# EP4CE55F23C8N_A.net
KiCad netlist of a schematic drawn in Altium Designer
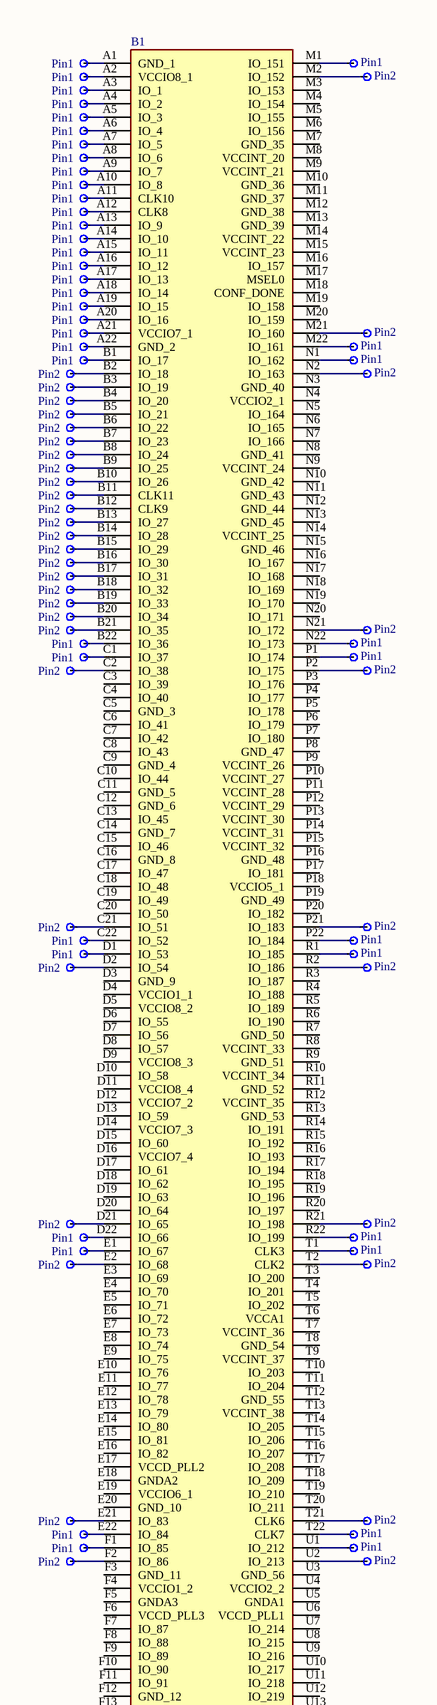
[diagram p0: EP4CE55F23C8N_A.SchDoc, top]
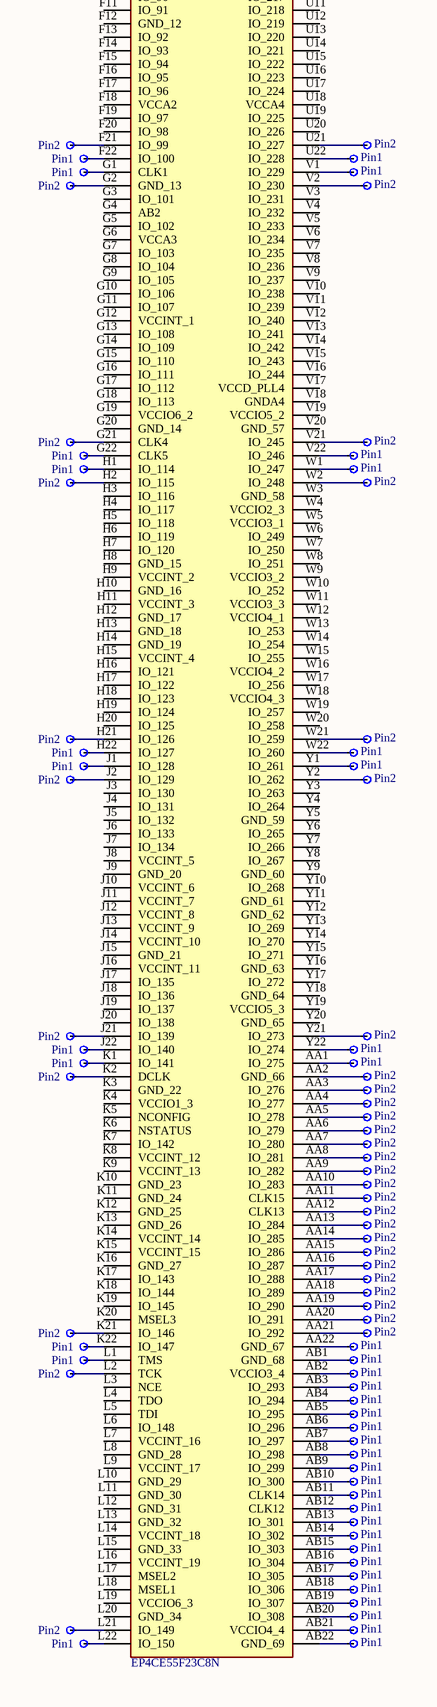
[diagram p1: EP4CE55F23C8N_A.SchDoc, bottom]

(export (version "E")
  (design (tool "Eeschema 10.0.6"))
  (components
    (comp (ref "B1")
      (value "EP4CE55F23C8N")
      (footprint "BGA484C100P22X22_2300X2300X240")
      (description "FPGA - Field Programmable Gate Array FPGA - Cyclone IV E 3491 LABs 324 IOs")
      (fields (field (name "MOUSER PART NUMBER") "989-EP4CE55F23C8N"))
      (libsource (lib "EP4CE55F23C8N") (part "EP4CE55F23C8N"))
    )
    (comp (ref "J1") (value "Pin1") (footprint "Pin1") (libsource (lib "Schlib1") (part "Pin1")))
    (comp (ref "J2") (value "Pin1") (footprint "Pin1") (libsource (lib "Schlib1") (part "Pin1")))
    (comp (ref "J3") (value "Pin1") (footprint "Pin1") (libsource (lib "Schlib1") (part "Pin1")))
    (comp (ref "J4") (value "Pin2") (footprint "Pin1") (libsource (lib "Schlib1") (part "Pin1")))
    (comp (ref "J5") (value "Pin1") (footprint "Pin1") (libsource (lib "Schlib1") (part "Pin1")))
    (comp (ref "J6") (value "Pin1") (footprint "Pin1") (libsource (lib "Schlib1") (part "Pin1")))
    (comp (ref "J7") (value "Pin1") (footprint "Pin1") (libsource (lib "Schlib1") (part "Pin1")))
    (comp (ref "J8") (value "Pin1") (footprint "Pin1") (libsource (lib "Schlib1") (part "Pin1")))
    (comp (ref "J9") (value "Pin1") (footprint "Pin1") (libsource (lib "Schlib1") (part "Pin1")))
    (comp (ref "J10") (value "Pin1") (footprint "Pin1") (libsource (lib "Schlib1") (part "Pin1")))
    (comp (ref "J11") (value "Pin1") (footprint "Pin1") (libsource (lib "Schlib1") (part "Pin1")))
    (comp (ref "J12") (value "Pin1") (footprint "Pin1") (libsource (lib "Schlib1") (part "Pin1")))
    (comp (ref "J13") (value "Pin1") (footprint "Pin1") (libsource (lib "Schlib1") (part "Pin1")))
    (comp (ref "J14") (value "Pin1") (footprint "Pin1") (libsource (lib "Schlib1") (part "Pin1")))
    (comp (ref "J15") (value "Pin1") (footprint "Pin1") (libsource (lib "Schlib1") (part "Pin1")))
    (comp (ref "J16") (value "Pin1") (footprint "Pin1") (libsource (lib "Schlib1") (part "Pin1")))
    (comp (ref "J17") (value "Pin1") (footprint "Pin1") (libsource (lib "Schlib1") (part "Pin1")))
    (comp (ref "J18") (value "Pin1") (footprint "Pin1") (libsource (lib "Schlib1") (part "Pin1")))
    (comp (ref "J19") (value "Pin1") (footprint "Pin1") (libsource (lib "Schlib1") (part "Pin1")))
    (comp (ref "J20") (value "Pin1") (footprint "Pin1") (libsource (lib "Schlib1") (part "Pin1")))
    (comp (ref "J21") (value "Pin1") (footprint "Pin1") (libsource (lib "Schlib1") (part "Pin1")))
    (comp (ref "J22") (value "Pin1") (footprint "Pin1") (libsource (lib "Schlib1") (part "Pin1")))
    (comp (ref "J23") (value "Pin1") (footprint "Pin1") (libsource (lib "Schlib1") (part "Pin1")))
    (comp (ref "J24") (value "Pin2") (footprint "Pin1") (libsource (lib "Schlib1") (part "Pin1")))
    (comp (ref "J25") (value "Pin1") (footprint "Pin1") (libsource (lib "Schlib1") (part "Pin1")))
    (comp (ref "J26") (value "Pin1") (footprint "Pin1") (libsource (lib "Schlib1") (part "Pin1")))
    (comp (ref "J27") (value "Pin1") (footprint "Pin1") (libsource (lib "Schlib1") (part "Pin1")))
    (comp (ref "J28") (value "Pin1") (footprint "Pin1") (libsource (lib "Schlib1") (part "Pin1")))
    (comp (ref "J29") (value "Pin2") (footprint "Pin1") (libsource (lib "Schlib1") (part "Pin1")))
    (comp (ref "J30") (value "Pin2") (footprint "Pin1") (libsource (lib "Schlib1") (part "Pin1")))
    (comp (ref "J31") (value "Pin2") (footprint "Pin1") (libsource (lib "Schlib1") (part "Pin1")))
    (comp (ref "J32") (value "Pin2") (footprint "Pin1") (libsource (lib "Schlib1") (part "Pin1")))
    (comp (ref "J33") (value "Pin2") (footprint "Pin1") (libsource (lib "Schlib1") (part "Pin1")))
    (comp (ref "J34") (value "Pin2") (footprint "Pin1") (libsource (lib "Schlib1") (part "Pin1")))
    (comp (ref "J35") (value "Pin2") (footprint "Pin1") (libsource (lib "Schlib1") (part "Pin1")))
    (comp (ref "J36") (value "Pin2") (footprint "Pin1") (libsource (lib "Schlib1") (part "Pin1")))
    (comp (ref "J37") (value "Pin2") (footprint "Pin1") (libsource (lib "Schlib1") (part "Pin1")))
    (comp (ref "J38") (value "Pin2") (footprint "Pin1") (libsource (lib "Schlib1") (part "Pin1")))
    (comp (ref "J39") (value "Pin2") (footprint "Pin1") (libsource (lib "Schlib1") (part "Pin1")))
    (comp (ref "J40") (value "Pin2") (footprint "Pin1") (libsource (lib "Schlib1") (part "Pin1")))
    (comp (ref "J41") (value "Pin2") (footprint "Pin1") (libsource (lib "Schlib1") (part "Pin1")))
    (comp (ref "J42") (value "Pin2") (footprint "Pin1") (libsource (lib "Schlib1") (part "Pin1")))
    (comp (ref "J43") (value "Pin2") (footprint "Pin1") (libsource (lib "Schlib1") (part "Pin1")))
    (comp (ref "J44") (value "Pin2") (footprint "Pin1") (libsource (lib "Schlib1") (part "Pin1")))
    (comp (ref "J45") (value "Pin2") (footprint "Pin1") (libsource (lib "Schlib1") (part "Pin1")))
    (comp (ref "J46") (value "Pin2") (footprint "Pin1") (libsource (lib "Schlib1") (part "Pin1")))
    (comp (ref "J47") (value "Pin2") (footprint "Pin1") (libsource (lib "Schlib1") (part "Pin1")))
    (comp (ref "J48") (value "Pin2") (footprint "Pin1") (libsource (lib "Schlib1") (part "Pin1")))
    (comp (ref "J49") (value "Pin2") (footprint "Pin1") (libsource (lib "Schlib1") (part "Pin1")))
    (comp (ref "J50") (value "Pin2") (footprint "Pin1") (libsource (lib "Schlib1") (part "Pin1")))
    (comp (ref "J51") (value "Pin1") (footprint "Pin1") (libsource (lib "Schlib1") (part "Pin1")))
    (comp (ref "J52") (value "Pin1") (footprint "Pin1") (libsource (lib "Schlib1") (part "Pin1")))
    (comp (ref "J53") (value "Pin1") (footprint "Pin1") (libsource (lib "Schlib1") (part "Pin1")))
    (comp (ref "J54") (value "Pin1") (footprint "Pin1") (libsource (lib "Schlib1") (part "Pin1")))
    (comp (ref "J55") (value "Pin2") (footprint "Pin1") (libsource (lib "Schlib1") (part "Pin1")))
    (comp (ref "J56") (value "Pin2") (footprint "Pin1") (libsource (lib "Schlib1") (part "Pin1")))
    (comp (ref "J57") (value "Pin2") (footprint "Pin1") (libsource (lib "Schlib1") (part "Pin1")))
    (comp (ref "J58") (value "Pin2") (footprint "Pin1") (libsource (lib "Schlib1") (part "Pin1")))
    (comp (ref "J59") (value "Pin1") (footprint "Pin1") (libsource (lib "Schlib1") (part "Pin1")))
    (comp (ref "J60") (value "Pin1") (footprint "Pin1") (libsource (lib "Schlib1") (part "Pin1")))
    (comp (ref "J61") (value "Pin1") (footprint "Pin1") (libsource (lib "Schlib1") (part "Pin1")))
    (comp (ref "J62") (value "Pin1") (footprint "Pin1") (libsource (lib "Schlib1") (part "Pin1")))
    (comp (ref "J63") (value "Pin2") (footprint "Pin1") (libsource (lib "Schlib1") (part "Pin1")))
    (comp (ref "J64") (value "Pin2") (footprint "Pin1") (libsource (lib "Schlib1") (part "Pin1")))
    (comp (ref "J65") (value "Pin2") (footprint "Pin1") (libsource (lib "Schlib1") (part "Pin1")))
    (comp (ref "J66") (value "Pin2") (footprint "Pin1") (libsource (lib "Schlib1") (part "Pin1")))
    (comp (ref "J67") (value "Pin1") (footprint "Pin1") (libsource (lib "Schlib1") (part "Pin1")))
    (comp (ref "J68") (value "Pin1") (footprint "Pin1") (libsource (lib "Schlib1") (part "Pin1")))
    (comp (ref "J69") (value "Pin1") (footprint "Pin1") (libsource (lib "Schlib1") (part "Pin1")))
    (comp (ref "J70") (value "Pin1") (footprint "Pin1") (libsource (lib "Schlib1") (part "Pin1")))
    (comp (ref "J71") (value "Pin2") (footprint "Pin1") (libsource (lib "Schlib1") (part "Pin1")))
    (comp (ref "J72") (value "Pin2") (footprint "Pin1") (libsource (lib "Schlib1") (part "Pin1")))
    (comp (ref "J73") (value "Pin2") (footprint "Pin1") (libsource (lib "Schlib1") (part "Pin1")))
    (comp (ref "J74") (value "Pin2") (footprint "Pin1") (libsource (lib "Schlib1") (part "Pin1")))
    (comp (ref "J75") (value "Pin1") (footprint "Pin1") (libsource (lib "Schlib1") (part "Pin1")))
    (comp (ref "J76") (value "Pin1") (footprint "Pin1") (libsource (lib "Schlib1") (part "Pin1")))
    (comp (ref "J77") (value "Pin1") (footprint "Pin1") (libsource (lib "Schlib1") (part "Pin1")))
    (comp (ref "J78") (value "Pin1") (footprint "Pin1") (libsource (lib "Schlib1") (part "Pin1")))
    (comp (ref "J79") (value "Pin2") (footprint "Pin1") (libsource (lib "Schlib1") (part "Pin1")))
    (comp (ref "J80") (value "Pin2") (footprint "Pin1") (libsource (lib "Schlib1") (part "Pin1")))
    (comp (ref "J81") (value "Pin2") (footprint "Pin1") (libsource (lib "Schlib1") (part "Pin1")))
    (comp (ref "J82") (value "Pin2") (footprint "Pin1") (libsource (lib "Schlib1") (part "Pin1")))
    (comp (ref "J83") (value "Pin1") (footprint "Pin1") (libsource (lib "Schlib1") (part "Pin1")))
    (comp (ref "J84") (value "Pin1") (footprint "Pin1") (libsource (lib "Schlib1") (part "Pin1")))
    (comp (ref "J85") (value "Pin1") (footprint "Pin1") (libsource (lib "Schlib1") (part "Pin1")))
    (comp (ref "J86") (value "Pin1") (footprint "Pin1") (libsource (lib "Schlib1") (part "Pin1")))
    (comp (ref "J87") (value "Pin2") (footprint "Pin1") (libsource (lib "Schlib1") (part "Pin1")))
    (comp (ref "J88") (value "Pin2") (footprint "Pin1") (libsource (lib "Schlib1") (part "Pin1")))
    (comp (ref "J89") (value "Pin2") (footprint "Pin1") (libsource (lib "Schlib1") (part "Pin1")))
    (comp (ref "J90") (value "Pin2") (footprint "Pin1") (libsource (lib "Schlib1") (part "Pin1")))
    (comp (ref "J91") (value "Pin1") (footprint "Pin1") (libsource (lib "Schlib1") (part "Pin1")))
    (comp (ref "J92") (value "Pin1") (footprint "Pin1") (libsource (lib "Schlib1") (part "Pin1")))
    (comp (ref "J93") (value "Pin1") (footprint "Pin1") (libsource (lib "Schlib1") (part "Pin1")))
    (comp (ref "J94") (value "Pin1") (footprint "Pin1") (libsource (lib "Schlib1") (part "Pin1")))
    (comp (ref "J95") (value "Pin2") (footprint "Pin1") (libsource (lib "Schlib1") (part "Pin1")))
    (comp (ref "J96") (value "Pin2") (footprint "Pin1") (libsource (lib "Schlib1") (part "Pin1")))
    (comp (ref "J97") (value "Pin2") (footprint "Pin1") (libsource (lib "Schlib1") (part "Pin1")))
    (comp (ref "J98") (value "Pin2") (footprint "Pin1") (libsource (lib "Schlib1") (part "Pin1")))
    (comp (ref "J99") (value "Pin1") (footprint "Pin1") (libsource (lib "Schlib1") (part "Pin1")))
    (comp (ref "J100") (value "Pin1") (footprint "Pin1") (libsource (lib "Schlib1") (part "Pin1")))
    (comp (ref "J101") (value "Pin1") (footprint "Pin1") (libsource (lib "Schlib1") (part "Pin1")))
    (comp (ref "J102") (value "Pin1") (footprint "Pin1") (libsource (lib "Schlib1") (part "Pin1")))
    (comp (ref "J103") (value "Pin2") (footprint "Pin1") (libsource (lib "Schlib1") (part "Pin1")))
    (comp (ref "J104") (value "Pin2") (footprint "Pin1") (libsource (lib "Schlib1") (part "Pin1")))
    (comp (ref "J105") (value "Pin2") (footprint "Pin1") (libsource (lib "Schlib1") (part "Pin1")))
    (comp (ref "J106") (value "Pin2") (footprint "Pin1") (libsource (lib "Schlib1") (part "Pin1")))
    (comp (ref "J107") (value "Pin1") (footprint "Pin1") (libsource (lib "Schlib1") (part "Pin1")))
    (comp (ref "J108") (value "Pin1") (footprint "Pin1") (libsource (lib "Schlib1") (part "Pin1")))
    (comp (ref "J109") (value "Pin1") (footprint "Pin1") (libsource (lib "Schlib1") (part "Pin1")))
    (comp (ref "J110") (value "Pin1") (footprint "Pin1") (libsource (lib "Schlib1") (part "Pin1")))
    (comp (ref "J111") (value "Pin2") (footprint "Pin1") (libsource (lib "Schlib1") (part "Pin1")))
    (comp (ref "J112") (value "Pin2") (footprint "Pin1") (libsource (lib "Schlib1") (part "Pin1")))
    (comp (ref "J113") (value "Pin2") (footprint "Pin1") (libsource (lib "Schlib1") (part "Pin1")))
    (comp (ref "J114") (value "Pin2") (footprint "Pin1") (libsource (lib "Schlib1") (part "Pin1")))
    (comp (ref "J115") (value "Pin2") (footprint "Pin1") (libsource (lib "Schlib1") (part "Pin1")))
    (comp (ref "J116") (value "Pin2") (footprint "Pin1") (libsource (lib "Schlib1") (part "Pin1")))
    (comp (ref "J117") (value "Pin2") (footprint "Pin1") (libsource (lib "Schlib1") (part "Pin1")))
    (comp (ref "J118") (value "Pin2") (footprint "Pin1") (libsource (lib "Schlib1") (part "Pin1")))
    (comp (ref "J119") (value "Pin2") (footprint "Pin1") (libsource (lib "Schlib1") (part "Pin1")))
    (comp (ref "J120") (value "Pin2") (footprint "Pin1") (libsource (lib "Schlib1") (part "Pin1")))
    (comp (ref "J121") (value "Pin2") (footprint "Pin1") (libsource (lib "Schlib1") (part "Pin1")))
    (comp (ref "J122") (value "Pin2") (footprint "Pin1") (libsource (lib "Schlib1") (part "Pin1")))
    (comp (ref "J123") (value "Pin2") (footprint "Pin1") (libsource (lib "Schlib1") (part "Pin1")))
    (comp (ref "J124") (value "Pin2") (footprint "Pin1") (libsource (lib "Schlib1") (part "Pin1")))
    (comp (ref "J125") (value "Pin2") (footprint "Pin1") (libsource (lib "Schlib1") (part "Pin1")))
    (comp (ref "J126") (value "Pin2") (footprint "Pin1") (libsource (lib "Schlib1") (part "Pin1")))
    (comp (ref "J127") (value "Pin2") (footprint "Pin1") (libsource (lib "Schlib1") (part "Pin1")))
    (comp (ref "J128") (value "Pin2") (footprint "Pin1") (libsource (lib "Schlib1") (part "Pin1")))
    (comp (ref "J129") (value "Pin2") (footprint "Pin1") (libsource (lib "Schlib1") (part "Pin1")))
    (comp (ref "J130") (value "Pin2") (footprint "Pin1") (libsource (lib "Schlib1") (part "Pin1")))
    (comp (ref "J131") (value "Pin2") (footprint "Pin1") (libsource (lib "Schlib1") (part "Pin1")))
    (comp (ref "J132") (value "Pin2") (footprint "Pin1") (libsource (lib "Schlib1") (part "Pin1")))
    (comp (ref "J133") (value "Pin1") (footprint "Pin1") (libsource (lib "Schlib1") (part "Pin1")))
    (comp (ref "J134") (value "Pin1") (footprint "Pin1") (libsource (lib "Schlib1") (part "Pin1")))
    (comp (ref "J135") (value "Pin1") (footprint "Pin1") (libsource (lib "Schlib1") (part "Pin1")))
    (comp (ref "J136") (value "Pin1") (footprint "Pin1") (libsource (lib "Schlib1") (part "Pin1")))
    (comp (ref "J137") (value "Pin2") (footprint "Pin1") (libsource (lib "Schlib1") (part "Pin1")))
    (comp (ref "J138") (value "Pin1") (footprint "Pin1") (libsource (lib "Schlib1") (part "Pin1")))
    (comp (ref "J139") (value "Pin1") (footprint "Pin1") (libsource (lib "Schlib1") (part "Pin1")))
    (comp (ref "J140") (value "Pin1") (footprint "Pin1") (libsource (lib "Schlib1") (part "Pin1")))
    (comp (ref "J141") (value "Pin1") (footprint "Pin1") (libsource (lib "Schlib1") (part "Pin1")))
    (comp (ref "J142") (value "Pin1") (footprint "Pin1") (libsource (lib "Schlib1") (part "Pin1")))
    (comp (ref "J143") (value "Pin1") (footprint "Pin1") (libsource (lib "Schlib1") (part "Pin1")))
    (comp (ref "J144") (value "Pin1") (footprint "Pin1") (libsource (lib "Schlib1") (part "Pin1")))
    (comp (ref "J145") (value "Pin1") (footprint "Pin1") (libsource (lib "Schlib1") (part "Pin1")))
    (comp (ref "J146") (value "Pin1") (footprint "Pin1") (libsource (lib "Schlib1") (part "Pin1")))
    (comp (ref "J147") (value "Pin1") (footprint "Pin1") (libsource (lib "Schlib1") (part "Pin1")))
    (comp (ref "J148") (value "Pin1") (footprint "Pin1") (libsource (lib "Schlib1") (part "Pin1")))
    (comp (ref "J149") (value "Pin1") (footprint "Pin1") (libsource (lib "Schlib1") (part "Pin1")))
    (comp (ref "J150") (value "Pin1") (footprint "Pin1") (libsource (lib "Schlib1") (part "Pin1")))
    (comp (ref "J151") (value "Pin1") (footprint "Pin1") (libsource (lib "Schlib1") (part "Pin1")))
    (comp (ref "J152") (value "Pin1") (footprint "Pin1") (libsource (lib "Schlib1") (part "Pin1")))
    (comp (ref "J153") (value "Pin1") (footprint "Pin1") (libsource (lib "Schlib1") (part "Pin1")))
    (comp (ref "J154") (value "Pin1") (footprint "Pin1") (libsource (lib "Schlib1") (part "Pin1")))
    (comp (ref "J155") (value "Pin1") (footprint "Pin1") (libsource (lib "Schlib1") (part "Pin1")))
    (comp (ref "J156") (value "Pin1") (footprint "Pin1") (libsource (lib "Schlib1") (part "Pin1")))
    (comp (ref "J157") (value "Pin2") (footprint "Pin1") (libsource (lib "Schlib1") (part "Pin1")))
    (comp (ref "J158") (value "Pin1") (footprint "Pin1") (libsource (lib "Schlib1") (part "Pin1")))
    (comp (ref "J159") (value "Pin1") (footprint "Pin1") (libsource (lib "Schlib1") (part "Pin1")))
    (comp (ref "J160") (value "Pin1") (footprint "Pin1") (libsource (lib "Schlib1") (part "Pin1")))
  )
  (nets
    (net (code "1") (name "Net-(B1-CLK1)") (class "Default")
      (node (ref "B1") (pin "G1") (pinfunction "CLK1_G1") (pintype "passive"))
      (node (ref "J85") (pin "1") (pinfunction "1_1") (pintype "passive"))
    )
    (net (code "2") (name "Net-(B1-CLK2)") (class "Default")
      (node (ref "B1") (pin "T2") (pinfunction "CLK2_T2") (pintype "passive"))
      (node (ref "J72") (pin "1") (pinfunction "1_1") (pintype "passive"))
    )
    (net (code "3") (name "Net-(B1-CLK3)") (class "Default")
      (node (ref "B1") (pin "T1") (pinfunction "CLK3_T1") (pintype "passive"))
      (node (ref "J70") (pin "1") (pinfunction "1_1") (pintype "passive"))
    )
    (net (code "4") (name "Net-(B1-CLK4)") (class "Default")
      (node (ref "B1") (pin "G21") (pinfunction "CLK4_G21") (pintype "passive"))
      (node (ref "J89") (pin "1") (pinfunction "1_1") (pintype "passive"))
    )
    (net (code "5") (name "Net-(B1-CLK5)") (class "Default")
      (node (ref "B1") (pin "G22") (pinfunction "CLK5_G22") (pintype "passive"))
      (node (ref "J91") (pin "1") (pinfunction "1_1") (pintype "passive"))
    )
    (net (code "6") (name "Net-(B1-CLK6)") (class "Default")
      (node (ref "B1") (pin "T21") (pinfunction "CLK6_T21") (pintype "passive"))
      (node (ref "J74") (pin "1") (pinfunction "1_1") (pintype "passive"))
    )
    (net (code "7") (name "Net-(B1-CLK7)") (class "Default")
      (node (ref "B1") (pin "T22") (pinfunction "CLK7_T22") (pintype "passive"))
      (node (ref "J76") (pin "1") (pinfunction "1_1") (pintype "passive"))
    )
    (net (code "8") (name "Net-(B1-CLK8)") (class "Default")
      (node (ref "B1") (pin "A12") (pinfunction "CLK8_A12") (pintype "passive"))
      (node (ref "J14") (pin "1") (pinfunction "1_1") (pintype "passive"))
    )
    (net (code "9") (name "Net-(B1-CLK9)") (class "Default")
      (node (ref "B1") (pin "B12") (pinfunction "CLK9_B12") (pintype "passive"))
      (node (ref "J40") (pin "1") (pinfunction "1_1") (pintype "passive"))
    )
    (net (code "10") (name "Net-(B1-CLK10)") (class "Default")
      (node (ref "B1") (pin "A11") (pinfunction "CLK10_A11") (pintype "passive"))
      (node (ref "J13") (pin "1") (pinfunction "1_1") (pintype "passive"))
    )
    (net (code "11") (name "Net-(B1-CLK11)") (class "Default")
      (node (ref "B1") (pin "B11") (pinfunction "CLK11_B11") (pintype "passive"))
      (node (ref "J39") (pin "1") (pinfunction "1_1") (pintype "passive"))
    )
    (net (code "12") (name "Net-(B1-CLK12)") (class "Default")
      (node (ref "B1") (pin "AB12") (pinfunction "CLK12_AB12") (pintype "passive"))
      (node (ref "J148") (pin "1") (pinfunction "1_1") (pintype "passive"))
    )
    (net (code "13") (name "Net-(B1-CLK13)") (class "Default")
      (node (ref "B1") (pin "AA12") (pinfunction "CLK13_AA12") (pintype "passive"))
      (node (ref "J122") (pin "1") (pinfunction "1_1") (pintype "passive"))
    )
    (net (code "14") (name "Net-(B1-CLK14)") (class "Default")
      (node (ref "B1") (pin "AB11") (pinfunction "CLK14_AB11") (pintype "passive"))
      (node (ref "J147") (pin "1") (pinfunction "1_1") (pintype "passive"))
    )
    (net (code "15") (name "Net-(B1-CLK15)") (class "Default")
      (node (ref "B1") (pin "AA11") (pinfunction "CLK15_AA11") (pintype "passive"))
      (node (ref "J121") (pin "1") (pinfunction "1_1") (pintype "passive"))
    )
    (net (code "16") (name "Net-(B1-DCLK)") (class "Default")
      (node (ref "B1") (pin "K2") (pinfunction "DCLK_K2") (pintype "passive"))
      (node (ref "J111") (pin "1") (pinfunction "1_1") (pintype "passive"))
    )
    (net (code "17") (name "Net-(B1-GND_1)") (class "Default")
      (node (ref "B1") (pin "A1") (pinfunction "GND_1_A1") (pintype "passive"))
      (node (ref "J1") (pin "1") (pinfunction "1_1") (pintype "passive"))
    )
    (net (code "18") (name "Net-(B1-GND_2)") (class "Default")
      (node (ref "B1") (pin "A22") (pinfunction "GND_2_A22") (pintype "passive"))
      (node (ref "J25") (pin "1") (pinfunction "1_1") (pintype "passive"))
    )
    (net (code "19") (name "Net-(B1-GND_13)") (class "Default")
      (node (ref "B1") (pin "G2") (pinfunction "GND_13_G2") (pintype "passive"))
      (node (ref "J87") (pin "1") (pinfunction "1_1") (pintype "passive"))
    )
    (net (code "20") (name "Net-(B1-GND_66)") (class "Default")
      (node (ref "B1") (pin "AA2") (pinfunction "GND_66_AA2") (pintype "passive"))
      (node (ref "J112") (pin "1") (pinfunction "1_1") (pintype "passive"))
    )
    (net (code "21") (name "Net-(B1-GND_67)") (class "Default")
      (node (ref "B1") (pin "AA22") (pinfunction "GND_67_AA22") (pintype "passive"))
      (node (ref "J134") (pin "1") (pinfunction "1_1") (pintype "passive"))
    )
    (net (code "22") (name "Net-(B1-GND_68)") (class "Default")
      (node (ref "B1") (pin "AB1") (pinfunction "GND_68_AB1") (pintype "passive"))
      (node (ref "J136") (pin "1") (pinfunction "1_1") (pintype "passive"))
    )
    (net (code "23") (name "Net-(B1-GND_69)") (class "Default")
      (node (ref "B1") (pin "AB22") (pinfunction "GND_69_AB22") (pintype "passive"))
      (node (ref "J160") (pin "1") (pinfunction "1_1") (pintype "passive"))
    )
    (net (code "24") (name "Net-(B1-IO_1)") (class "Default")
      (node (ref "B1") (pin "A3") (pinfunction "IO_1_A3") (pintype "passive"))
      (node (ref "J5") (pin "1") (pinfunction "1_1") (pintype "passive"))
    )
    (net (code "25") (name "Net-(B1-IO_2)") (class "Default")
      (node (ref "B1") (pin "A4") (pinfunction "IO_2_A4") (pintype "passive"))
      (node (ref "J6") (pin "1") (pinfunction "1_1") (pintype "passive"))
    )
    (net (code "26") (name "Net-(B1-IO_3)") (class "Default")
      (node (ref "B1") (pin "A5") (pinfunction "IO_3_A5") (pintype "passive"))
      (node (ref "J7") (pin "1") (pinfunction "1_1") (pintype "passive"))
    )
    (net (code "27") (name "Net-(B1-IO_4)") (class "Default")
      (node (ref "B1") (pin "A6") (pinfunction "IO_4_A6") (pintype "passive"))
      (node (ref "J8") (pin "1") (pinfunction "1_1") (pintype "passive"))
    )
    (net (code "28") (name "Net-(B1-IO_5)") (class "Default")
      (node (ref "B1") (pin "A7") (pinfunction "IO_5_A7") (pintype "passive"))
      (node (ref "J9") (pin "1") (pinfunction "1_1") (pintype "passive"))
    )
    (net (code "29") (name "Net-(B1-IO_6)") (class "Default")
      (node (ref "B1") (pin "A8") (pinfunction "IO_6_A8") (pintype "passive"))
      (node (ref "J10") (pin "1") (pinfunction "1_1") (pintype "passive"))
    )
    (net (code "30") (name "Net-(B1-IO_7)") (class "Default")
      (node (ref "B1") (pin "A9") (pinfunction "IO_7_A9") (pintype "passive"))
      (node (ref "J11") (pin "1") (pinfunction "1_1") (pintype "passive"))
    )
    (net (code "31") (name "Net-(B1-IO_8)") (class "Default")
      (node (ref "B1") (pin "A10") (pinfunction "IO_8_A10") (pintype "passive"))
      (node (ref "J12") (pin "1") (pinfunction "1_1") (pintype "passive"))
    )
    (net (code "32") (name "Net-(B1-IO_9)") (class "Default")
      (node (ref "B1") (pin "A13") (pinfunction "IO_9_A13") (pintype "passive"))
      (node (ref "J15") (pin "1") (pinfunction "1_1") (pintype "passive"))
    )
    (net (code "33") (name "Net-(B1-IO_10)") (class "Default")
      (node (ref "B1") (pin "A14") (pinfunction "IO_10_A14") (pintype "passive"))
      (node (ref "J16") (pin "1") (pinfunction "1_1") (pintype "passive"))
    )
    (net (code "34") (name "Net-(B1-IO_11)") (class "Default")
      (node (ref "B1") (pin "A15") (pinfunction "IO_11_A15") (pintype "passive"))
      (node (ref "J17") (pin "1") (pinfunction "1_1") (pintype "passive"))
    )
    (net (code "35") (name "Net-(B1-IO_12)") (class "Default")
      (node (ref "B1") (pin "A16") (pinfunction "IO_12_A16") (pintype "passive"))
      (node (ref "J18") (pin "1") (pinfunction "1_1") (pintype "passive"))
    )
    (net (code "36") (name "Net-(B1-IO_13)") (class "Default")
      (node (ref "B1") (pin "A17") (pinfunction "IO_13_A17") (pintype "passive"))
      (node (ref "J19") (pin "1") (pinfunction "1_1") (pintype "passive"))
    )
    (net (code "37") (name "Net-(B1-IO_14)") (class "Default")
      (node (ref "B1") (pin "A18") (pinfunction "IO_14_A18") (pintype "passive"))
      (node (ref "J20") (pin "1") (pinfunction "1_1") (pintype "passive"))
    )
    (net (code "38") (name "Net-(B1-IO_15)") (class "Default")
      (node (ref "B1") (pin "A19") (pinfunction "IO_15_A19") (pintype "passive"))
      (node (ref "J21") (pin "1") (pinfunction "1_1") (pintype "passive"))
    )
    (net (code "39") (name "Net-(B1-IO_16)") (class "Default")
      (node (ref "B1") (pin "A20") (pinfunction "IO_16_A20") (pintype "passive"))
      (node (ref "J22") (pin "1") (pinfunction "1_1") (pintype "passive"))
    )
    (net (code "40") (name "Net-(B1-IO_17)") (class "Default")
      (node (ref "B1") (pin "B1") (pinfunction "IO_17_B1") (pintype "passive"))
      (node (ref "J27") (pin "1") (pinfunction "1_1") (pintype "passive"))
    )
    (net (code "41") (name "Net-(B1-IO_18)") (class "Default")
      (node (ref "B1") (pin "B2") (pinfunction "IO_18_B2") (pintype "passive"))
      (node (ref "J29") (pin "1") (pinfunction "1_1") (pintype "passive"))
    )
    (net (code "42") (name "Net-(B1-IO_19)") (class "Default")
      (node (ref "B1") (pin "B3") (pinfunction "IO_19_B3") (pintype "passive"))
      (node (ref "J31") (pin "1") (pinfunction "1_1") (pintype "passive"))
    )
    (net (code "43") (name "Net-(B1-IO_20)") (class "Default")
      (node (ref "B1") (pin "B4") (pinfunction "IO_20_B4") (pintype "passive"))
      (node (ref "J32") (pin "1") (pinfunction "1_1") (pintype "passive"))
    )
    (net (code "44") (name "Net-(B1-IO_21)") (class "Default")
      (node (ref "B1") (pin "B5") (pinfunction "IO_21_B5") (pintype "passive"))
      (node (ref "J33") (pin "1") (pinfunction "1_1") (pintype "passive"))
    )
    (net (code "45") (name "Net-(B1-IO_22)") (class "Default")
      (node (ref "B1") (pin "B6") (pinfunction "IO_22_B6") (pintype "passive"))
      (node (ref "J34") (pin "1") (pinfunction "1_1") (pintype "passive"))
    )
    (net (code "46") (name "Net-(B1-IO_23)") (class "Default")
      (node (ref "B1") (pin "B7") (pinfunction "IO_23_B7") (pintype "passive"))
      (node (ref "J35") (pin "1") (pinfunction "1_1") (pintype "passive"))
    )
    (net (code "47") (name "Net-(B1-IO_24)") (class "Default")
      (node (ref "B1") (pin "B8") (pinfunction "IO_24_B8") (pintype "passive"))
      (node (ref "J36") (pin "1") (pinfunction "1_1") (pintype "passive"))
    )
    (net (code "48") (name "Net-(B1-IO_25)") (class "Default")
      (node (ref "B1") (pin "B9") (pinfunction "IO_25_B9") (pintype "passive"))
      (node (ref "J37") (pin "1") (pinfunction "1_1") (pintype "passive"))
    )
    (net (code "49") (name "Net-(B1-IO_26)") (class "Default")
      (node (ref "B1") (pin "B10") (pinfunction "IO_26_B10") (pintype "passive"))
      (node (ref "J38") (pin "1") (pinfunction "1_1") (pintype "passive"))
    )
    (net (code "50") (name "Net-(B1-IO_27)") (class "Default")
      (node (ref "B1") (pin "B13") (pinfunction "IO_27_B13") (pintype "passive"))
      (node (ref "J41") (pin "1") (pinfunction "1_1") (pintype "passive"))
    )
    (net (code "51") (name "Net-(B1-IO_28)") (class "Default")
      (node (ref "B1") (pin "B14") (pinfunction "IO_28_B14") (pintype "passive"))
      (node (ref "J42") (pin "1") (pinfunction "1_1") (pintype "passive"))
    )
    (net (code "52") (name "Net-(B1-IO_29)") (class "Default")
      (node (ref "B1") (pin "B15") (pinfunction "IO_29_B15") (pintype "passive"))
      (node (ref "J43") (pin "1") (pinfunction "1_1") (pintype "passive"))
    )
    (net (code "53") (name "Net-(B1-IO_30)") (class "Default")
      (node (ref "B1") (pin "B16") (pinfunction "IO_30_B16") (pintype "passive"))
      (node (ref "J44") (pin "1") (pinfunction "1_1") (pintype "passive"))
    )
    (net (code "54") (name "Net-(B1-IO_31)") (class "Default")
      (node (ref "B1") (pin "B17") (pinfunction "IO_31_B17") (pintype "passive"))
      (node (ref "J45") (pin "1") (pinfunction "1_1") (pintype "passive"))
    )
    (net (code "55") (name "Net-(B1-IO_32)") (class "Default")
      (node (ref "B1") (pin "B18") (pinfunction "IO_32_B18") (pintype "passive"))
      (node (ref "J46") (pin "1") (pinfunction "1_1") (pintype "passive"))
    )
    (net (code "56") (name "Net-(B1-IO_33)") (class "Default")
      (node (ref "B1") (pin "B19") (pinfunction "IO_33_B19") (pintype "passive"))
      (node (ref "J47") (pin "1") (pinfunction "1_1") (pintype "passive"))
    )
    (net (code "57") (name "Net-(B1-IO_34)") (class "Default")
      (node (ref "B1") (pin "B20") (pinfunction "IO_34_B20") (pintype "passive"))
      (node (ref "J48") (pin "1") (pinfunction "1_1") (pintype "passive"))
    )
    (net (code "58") (name "Net-(B1-IO_35)") (class "Default")
      (node (ref "B1") (pin "B21") (pinfunction "IO_35_B21") (pintype "passive"))
      (node (ref "J49") (pin "1") (pinfunction "1_1") (pintype "passive"))
    )
    (net (code "59") (name "Net-(B1-IO_36)") (class "Default")
      (node (ref "B1") (pin "B22") (pinfunction "IO_36_B22") (pintype "passive"))
      (node (ref "J51") (pin "1") (pinfunction "1_1") (pintype "passive"))
    )
    (net (code "60") (name "Net-(B1-IO_37)") (class "Default")
      (node (ref "B1") (pin "C1") (pinfunction "IO_37_C1") (pintype "passive"))
      (node (ref "J53") (pin "1") (pinfunction "1_1") (pintype "passive"))
    )
    (net (code "61") (name "Net-(B1-IO_38)") (class "Default")
      (node (ref "B1") (pin "C2") (pinfunction "IO_38_C2") (pintype "passive"))
      (node (ref "J55") (pin "1") (pinfunction "1_1") (pintype "passive"))
    )
    (net (code "62") (name "Net-(B1-IO_51)") (class "Default")
      (node (ref "B1") (pin "C21") (pinfunction "IO_51_C21") (pintype "passive"))
      (node (ref "J57") (pin "1") (pinfunction "1_1") (pintype "passive"))
    )
    (net (code "63") (name "Net-(B1-IO_52)") (class "Default")
      (node (ref "B1") (pin "C22") (pinfunction "IO_52_C22") (pintype "passive"))
      (node (ref "J59") (pin "1") (pinfunction "1_1") (pintype "passive"))
    )
    (net (code "64") (name "Net-(B1-IO_53)") (class "Default")
      (node (ref "B1") (pin "D1") (pinfunction "IO_53_D1") (pintype "passive"))
      (node (ref "J61") (pin "1") (pinfunction "1_1") (pintype "passive"))
    )
    (net (code "65") (name "Net-(B1-IO_54)") (class "Default")
      (node (ref "B1") (pin "D2") (pinfunction "IO_54_D2") (pintype "passive"))
      (node (ref "J63") (pin "1") (pinfunction "1_1") (pintype "passive"))
    )
    (net (code "66") (name "Net-(B1-IO_65)") (class "Default")
      (node (ref "B1") (pin "D21") (pinfunction "IO_65_D21") (pintype "passive"))
      (node (ref "J65") (pin "1") (pinfunction "1_1") (pintype "passive"))
    )
    (net (code "67") (name "Net-(B1-IO_66)") (class "Default")
      (node (ref "B1") (pin "D22") (pinfunction "IO_66_D22") (pintype "passive"))
      (node (ref "J67") (pin "1") (pinfunction "1_1") (pintype "passive"))
    )
    (net (code "68") (name "Net-(B1-IO_67)") (class "Default")
      (node (ref "B1") (pin "E1") (pinfunction "IO_67_E1") (pintype "passive"))
      (node (ref "J69") (pin "1") (pinfunction "1_1") (pintype "passive"))
    )
    (net (code "69") (name "Net-(B1-IO_68)") (class "Default")
      (node (ref "B1") (pin "E2") (pinfunction "IO_68_E2") (pintype "passive"))
      (node (ref "J71") (pin "1") (pinfunction "1_1") (pintype "passive"))
    )
    (net (code "70") (name "Net-(B1-IO_83)") (class "Default")
      (node (ref "B1") (pin "E21") (pinfunction "IO_83_E21") (pintype "passive"))
      (node (ref "J73") (pin "1") (pinfunction "1_1") (pintype "passive"))
    )
    (net (code "71") (name "Net-(B1-IO_84)") (class "Default")
      (node (ref "B1") (pin "E22") (pinfunction "IO_84_E22") (pintype "passive"))
      (node (ref "J75") (pin "1") (pinfunction "1_1") (pintype "passive"))
    )
    (net (code "72") (name "Net-(B1-IO_85)") (class "Default")
      (node (ref "B1") (pin "F1") (pinfunction "IO_85_F1") (pintype "passive"))
      (node (ref "J77") (pin "1") (pinfunction "1_1") (pintype "passive"))
    )
    (net (code "73") (name "Net-(B1-IO_86)") (class "Default")
      (node (ref "B1") (pin "F2") (pinfunction "IO_86_F2") (pintype "passive"))
      (node (ref "J79") (pin "1") (pinfunction "1_1") (pintype "passive"))
    )
    (net (code "74") (name "Net-(B1-IO_99)") (class "Default")
      (node (ref "B1") (pin "F21") (pinfunction "IO_99_F21") (pintype "passive"))
      (node (ref "J81") (pin "1") (pinfunction "1_1") (pintype "passive"))
    )
    (net (code "75") (name "Net-(B1-IO_100)") (class "Default")
      (node (ref "B1") (pin "F22") (pinfunction "IO_100_F22") (pintype "passive"))
      (node (ref "J83") (pin "1") (pinfunction "1_1") (pintype "passive"))
    )
    (net (code "76") (name "Net-(B1-IO_114)") (class "Default")
      (node (ref "B1") (pin "H1") (pinfunction "IO_114_H1") (pintype "passive"))
      (node (ref "J93") (pin "1") (pinfunction "1_1") (pintype "passive"))
    )
    (net (code "77") (name "Net-(B1-IO_115)") (class "Default")
      (node (ref "B1") (pin "H2") (pinfunction "IO_115_H2") (pintype "passive"))
      (node (ref "J95") (pin "1") (pinfunction "1_1") (pintype "passive"))
    )
    (net (code "78") (name "Net-(B1-IO_126)") (class "Default")
      (node (ref "B1") (pin "H21") (pinfunction "IO_126_H21") (pintype "passive"))
      (node (ref "J97") (pin "1") (pinfunction "1_1") (pintype "passive"))
    )
    (net (code "79") (name "Net-(B1-IO_127)") (class "Default")
      (node (ref "B1") (pin "H22") (pinfunction "IO_127_H22") (pintype "passive"))
      (node (ref "J99") (pin "1") (pinfunction "1_1") (pintype "passive"))
    )
    (net (code "80") (name "Net-(B1-IO_128)") (class "Default")
      (node (ref "B1") (pin "J1") (pinfunction "IO_128_J1") (pintype "passive"))
      (node (ref "J101") (pin "1") (pinfunction "1_1") (pintype "passive"))
    )
    (net (code "81") (name "Net-(B1-IO_129)") (class "Default")
      (node (ref "B1") (pin "J2") (pinfunction "IO_129_J2") (pintype "passive"))
      (node (ref "J103") (pin "1") (pinfunction "1_1") (pintype "passive"))
    )
    (net (code "82") (name "Net-(B1-IO_139)") (class "Default")
      (node (ref "B1") (pin "J21") (pinfunction "IO_139_J21") (pintype "passive"))
      (node (ref "J105") (pin "1") (pinfunction "1_1") (pintype "passive"))
    )
    (net (code "83") (name "Net-(B1-IO_140)") (class "Default")
      (node (ref "B1") (pin "J22") (pinfunction "IO_140_J22") (pintype "passive"))
      (node (ref "J107") (pin "1") (pinfunction "1_1") (pintype "passive"))
    )
    (net (code "84") (name "Net-(B1-IO_141)") (class "Default")
      (node (ref "B1") (pin "K1") (pinfunction "IO_141_K1") (pintype "passive"))
      (node (ref "J109") (pin "1") (pinfunction "1_1") (pintype "passive"))
    )
    (net (code "85") (name "Net-(B1-IO_146)") (class "Default")
      (node (ref "B1") (pin "K21") (pinfunction "IO_146_K21") (pintype "passive"))
      (node (ref "J131") (pin "1") (pinfunction "1_1") (pintype "passive"))
    )
    (net (code "86") (name "Net-(B1-IO_147)") (class "Default")
      (node (ref "B1") (pin "K22") (pinfunction "IO_147_K22") (pintype "passive"))
      (node (ref "J133") (pin "1") (pinfunction "1_1") (pintype "passive"))
    )
    (net (code "87") (name "Net-(B1-IO_149)") (class "Default")
      (node (ref "B1") (pin "L21") (pinfunction "IO_149_L21") (pintype "passive"))
      (node (ref "J157") (pin "1") (pinfunction "1_1") (pintype "passive"))
    )
    (net (code "88") (name "Net-(B1-IO_150)") (class "Default")
      (node (ref "B1") (pin "L22") (pinfunction "IO_150_L22") (pintype "passive"))
      (node (ref "J159") (pin "1") (pinfunction "1_1") (pintype "passive"))
    )
    (net (code "89") (name "Net-(B1-IO_151)") (class "Default")
      (node (ref "B1") (pin "M1") (pinfunction "IO_151_M1") (pintype "passive"))
      (node (ref "J2") (pin "1") (pinfunction "1_1") (pintype "passive"))
    )
    (net (code "90") (name "Net-(B1-IO_152)") (class "Default")
      (node (ref "B1") (pin "M2") (pinfunction "IO_152_M2") (pintype "passive"))
      (node (ref "J4") (pin "1") (pinfunction "1_1") (pintype "passive"))
    )
    (net (code "91") (name "Net-(B1-IO_160)") (class "Default")
      (node (ref "B1") (pin "M21") (pinfunction "IO_160_M21") (pintype "passive"))
      (node (ref "J24") (pin "1") (pinfunction "1_1") (pintype "passive"))
    )
    (net (code "92") (name "Net-(B1-IO_161)") (class "Default")
      (node (ref "B1") (pin "M22") (pinfunction "IO_161_M22") (pintype "passive"))
      (node (ref "J26") (pin "1") (pinfunction "1_1") (pintype "passive"))
    )
    (net (code "93") (name "Net-(B1-IO_162)") (class "Default")
      (node (ref "B1") (pin "N1") (pinfunction "IO_162_N1") (pintype "passive"))
      (node (ref "J28") (pin "1") (pinfunction "1_1") (pintype "passive"))
    )
    (net (code "94") (name "Net-(B1-IO_163)") (class "Default")
      (node (ref "B1") (pin "N2") (pinfunction "IO_163_N2") (pintype "passive"))
      (node (ref "J30") (pin "1") (pinfunction "1_1") (pintype "passive"))
    )
    (net (code "95") (name "Net-(B1-IO_172)") (class "Default")
      (node (ref "B1") (pin "N21") (pinfunction "IO_172_N21") (pintype "passive"))
      (node (ref "J50") (pin "1") (pinfunction "1_1") (pintype "passive"))
    )
    (net (code "96") (name "Net-(B1-IO_173)") (class "Default")
      (node (ref "B1") (pin "N22") (pinfunction "IO_173_N22") (pintype "passive"))
      (node (ref "J52") (pin "1") (pinfunction "1_1") (pintype "passive"))
    )
    (net (code "97") (name "Net-(B1-IO_174)") (class "Default")
      (node (ref "B1") (pin "P1") (pinfunction "IO_174_P1") (pintype "passive"))
      (node (ref "J54") (pin "1") (pinfunction "1_1") (pintype "passive"))
    )
    (net (code "98") (name "Net-(B1-IO_175)") (class "Default")
      (node (ref "B1") (pin "P2") (pinfunction "IO_175_P2") (pintype "passive"))
      (node (ref "J56") (pin "1") (pinfunction "1_1") (pintype "passive"))
    )
    (net (code "99") (name "Net-(B1-IO_183)") (class "Default")
      (node (ref "B1") (pin "P21") (pinfunction "IO_183_P21") (pintype "passive"))
      (node (ref "J58") (pin "1") (pinfunction "1_1") (pintype "passive"))
    )
    (net (code "100") (name "Net-(B1-IO_184)") (class "Default")
      (node (ref "B1") (pin "P22") (pinfunction "IO_184_P22") (pintype "passive"))
      (node (ref "J60") (pin "1") (pinfunction "1_1") (pintype "passive"))
    )
    (net (code "101") (name "Net-(B1-IO_185)") (class "Default")
      (node (ref "B1") (pin "R1") (pinfunction "IO_185_R1") (pintype "passive"))
      (node (ref "J62") (pin "1") (pinfunction "1_1") (pintype "passive"))
    )
    (net (code "102") (name "Net-(B1-IO_186)") (class "Default")
      (node (ref "B1") (pin "R2") (pinfunction "IO_186_R2") (pintype "passive"))
      (node (ref "J64") (pin "1") (pinfunction "1_1") (pintype "passive"))
    )
    (net (code "103") (name "Net-(B1-IO_198)") (class "Default")
      (node (ref "B1") (pin "R21") (pinfunction "IO_198_R21") (pintype "passive"))
      (node (ref "J66") (pin "1") (pinfunction "1_1") (pintype "passive"))
    )
    (net (code "104") (name "Net-(B1-IO_199)") (class "Default")
      (node (ref "B1") (pin "R22") (pinfunction "IO_199_R22") (pintype "passive"))
      (node (ref "J68") (pin "1") (pinfunction "1_1") (pintype "passive"))
    )
    (net (code "105") (name "Net-(B1-IO_212)") (class "Default")
      (node (ref "B1") (pin "U1") (pinfunction "IO_212_U1") (pintype "passive"))
      (node (ref "J78") (pin "1") (pinfunction "1_1") (pintype "passive"))
    )
    (net (code "106") (name "Net-(B1-IO_213)") (class "Default")
      (node (ref "B1") (pin "U2") (pinfunction "IO_213_U2") (pintype "passive"))
      (node (ref "J80") (pin "1") (pinfunction "1_1") (pintype "passive"))
    )
    (net (code "107") (name "Net-(B1-IO_227)") (class "Default")
      (node (ref "B1") (pin "U21") (pinfunction "IO_227_U21") (pintype "passive"))
      (node (ref "J82") (pin "1") (pinfunction "1_1") (pintype "passive"))
    )
    (net (code "108") (name "Net-(B1-IO_228)") (class "Default")
      (node (ref "B1") (pin "U22") (pinfunction "IO_228_U22") (pintype "passive"))
      (node (ref "J84") (pin "1") (pinfunction "1_1") (pintype "passive"))
    )
    (net (code "109") (name "Net-(B1-IO_229)") (class "Default")
      (node (ref "B1") (pin "V1") (pinfunction "IO_229_V1") (pintype "passive"))
      (node (ref "J86") (pin "1") (pinfunction "1_1") (pintype "passive"))
    )
    (net (code "110") (name "Net-(B1-IO_230)") (class "Default")
      (node (ref "B1") (pin "V2") (pinfunction "IO_230_V2") (pintype "passive"))
      (node (ref "J88") (pin "1") (pinfunction "1_1") (pintype "passive"))
    )
    (net (code "111") (name "Net-(B1-IO_245)") (class "Default")
      (node (ref "B1") (pin "V21") (pinfunction "IO_245_V21") (pintype "passive"))
      (node (ref "J90") (pin "1") (pinfunction "1_1") (pintype "passive"))
    )
    (net (code "112") (name "Net-(B1-IO_246)") (class "Default")
      (node (ref "B1") (pin "V22") (pinfunction "IO_246_V22") (pintype "passive"))
      (node (ref "J92") (pin "1") (pinfunction "1_1") (pintype "passive"))
    )
    (net (code "113") (name "Net-(B1-IO_247)") (class "Default")
      (node (ref "B1") (pin "W1") (pinfunction "IO_247_W1") (pintype "passive"))
      (node (ref "J94") (pin "1") (pinfunction "1_1") (pintype "passive"))
    )
    (net (code "114") (name "Net-(B1-IO_248)") (class "Default")
      (node (ref "B1") (pin "W2") (pinfunction "IO_248_W2") (pintype "passive"))
      (node (ref "J96") (pin "1") (pinfunction "1_1") (pintype "passive"))
    )
    (net (code "115") (name "Net-(B1-IO_259)") (class "Default")
      (node (ref "B1") (pin "W21") (pinfunction "IO_259_W21") (pintype "passive"))
      (node (ref "J98") (pin "1") (pinfunction "1_1") (pintype "passive"))
    )
    (net (code "116") (name "Net-(B1-IO_260)") (class "Default")
      (node (ref "B1") (pin "W22") (pinfunction "IO_260_W22") (pintype "passive"))
      (node (ref "J100") (pin "1") (pinfunction "1_1") (pintype "passive"))
    )
    (net (code "117") (name "Net-(B1-IO_261)") (class "Default")
      (node (ref "B1") (pin "Y1") (pinfunction "IO_261_Y1") (pintype "passive"))
      (node (ref "J102") (pin "1") (pinfunction "1_1") (pintype "passive"))
    )
    (net (code "118") (name "Net-(B1-IO_262)") (class "Default")
      (node (ref "B1") (pin "Y2") (pinfunction "IO_262_Y2") (pintype "passive"))
      (node (ref "J104") (pin "1") (pinfunction "1_1") (pintype "passive"))
    )
    (net (code "119") (name "Net-(B1-IO_273)") (class "Default")
      (node (ref "B1") (pin "Y21") (pinfunction "IO_273_Y21") (pintype "passive"))
      (node (ref "J106") (pin "1") (pinfunction "1_1") (pintype "passive"))
    )
    (net (code "120") (name "Net-(B1-IO_274)") (class "Default")
      (node (ref "B1") (pin "Y22") (pinfunction "IO_274_Y22") (pintype "passive"))
      (node (ref "J108") (pin "1") (pinfunction "1_1") (pintype "passive"))
    )
    (net (code "121") (name "Net-(B1-IO_275)") (class "Default")
      (node (ref "B1") (pin "AA1") (pinfunction "IO_275_AA1") (pintype "passive"))
      (node (ref "J110") (pin "1") (pinfunction "1_1") (pintype "passive"))
    )
    (net (code "122") (name "Net-(B1-IO_276)") (class "Default")
      (node (ref "B1") (pin "AA3") (pinfunction "IO_276_AA3") (pintype "passive"))
      (node (ref "J113") (pin "1") (pinfunction "1_1") (pintype "passive"))
    )
    (net (code "123") (name "Net-(B1-IO_277)") (class "Default")
      (node (ref "B1") (pin "AA4") (pinfunction "IO_277_AA4") (pintype "passive"))
      (node (ref "J114") (pin "1") (pinfunction "1_1") (pintype "passive"))
    )
    (net (code "124") (name "Net-(B1-IO_278)") (class "Default")
      (node (ref "B1") (pin "AA5") (pinfunction "IO_278_AA5") (pintype "passive"))
      (node (ref "J115") (pin "1") (pinfunction "1_1") (pintype "passive"))
    )
    (net (code "125") (name "Net-(B1-IO_279)") (class "Default")
      (node (ref "B1") (pin "AA6") (pinfunction "IO_279_AA6") (pintype "passive"))
      (node (ref "J116") (pin "1") (pinfunction "1_1") (pintype "passive"))
    )
    (net (code "126") (name "Net-(B1-IO_280)") (class "Default")
      (node (ref "B1") (pin "AA7") (pinfunction "IO_280_AA7") (pintype "passive"))
      (node (ref "J117") (pin "1") (pinfunction "1_1") (pintype "passive"))
    )
    (net (code "127") (name "Net-(B1-IO_281)") (class "Default")
      (node (ref "B1") (pin "AA8") (pinfunction "IO_281_AA8") (pintype "passive"))
      (node (ref "J118") (pin "1") (pinfunction "1_1") (pintype "passive"))
    )
    (net (code "128") (name "Net-(B1-IO_282)") (class "Default")
      (node (ref "B1") (pin "AA9") (pinfunction "IO_282_AA9") (pintype "passive"))
      (node (ref "J119") (pin "1") (pinfunction "1_1") (pintype "passive"))
    )
    (net (code "129") (name "Net-(B1-IO_283)") (class "Default")
      (node (ref "B1") (pin "AA10") (pinfunction "IO_283_AA10") (pintype "passive"))
      (node (ref "J120") (pin "1") (pinfunction "1_1") (pintype "passive"))
    )
    (net (code "130") (name "Net-(B1-IO_284)") (class "Default")
      (node (ref "B1") (pin "AA13") (pinfunction "IO_284_AA13") (pintype "passive"))
      (node (ref "J123") (pin "1") (pinfunction "1_1") (pintype "passive"))
    )
    (net (code "131") (name "Net-(B1-IO_285)") (class "Default")
      (node (ref "B1") (pin "AA14") (pinfunction "IO_285_AA14") (pintype "passive"))
      (node (ref "J124") (pin "1") (pinfunction "1_1") (pintype "passive"))
    )
    (net (code "132") (name "Net-(B1-IO_286)") (class "Default")
      (node (ref "B1") (pin "AA15") (pinfunction "IO_286_AA15") (pintype "passive"))
      (node (ref "J125") (pin "1") (pinfunction "1_1") (pintype "passive"))
    )
    (net (code "133") (name "Net-(B1-IO_287)") (class "Default")
      (node (ref "B1") (pin "AA16") (pinfunction "IO_287_AA16") (pintype "passive"))
      (node (ref "J126") (pin "1") (pinfunction "1_1") (pintype "passive"))
    )
    (net (code "134") (name "Net-(B1-IO_288)") (class "Default")
      (node (ref "B1") (pin "AA17") (pinfunction "IO_288_AA17") (pintype "passive"))
      (node (ref "J127") (pin "1") (pinfunction "1_1") (pintype "passive"))
    )
    (net (code "135") (name "Net-(B1-IO_289)") (class "Default")
      (node (ref "B1") (pin "AA18") (pinfunction "IO_289_AA18") (pintype "passive"))
      (node (ref "J128") (pin "1") (pinfunction "1_1") (pintype "passive"))
    )
    (net (code "136") (name "Net-(B1-IO_290)") (class "Default")
      (node (ref "B1") (pin "AA19") (pinfunction "IO_290_AA19") (pintype "passive"))
      (node (ref "J129") (pin "1") (pinfunction "1_1") (pintype "passive"))
    )
    (net (code "137") (name "Net-(B1-IO_291)") (class "Default")
      (node (ref "B1") (pin "AA20") (pinfunction "IO_291_AA20") (pintype "passive"))
      (node (ref "J130") (pin "1") (pinfunction "1_1") (pintype "passive"))
    )
    (net (code "138") (name "Net-(B1-IO_292)") (class "Default")
      (node (ref "B1") (pin "AA21") (pinfunction "IO_292_AA21") (pintype "passive"))
      (node (ref "J132") (pin "1") (pinfunction "1_1") (pintype "passive"))
    )
    (net (code "139") (name "Net-(B1-IO_293)") (class "Default")
      (node (ref "B1") (pin "AB3") (pinfunction "IO_293_AB3") (pintype "passive"))
      (node (ref "J139") (pin "1") (pinfunction "1_1") (pintype "passive"))
    )
    (net (code "140") (name "Net-(B1-IO_294)") (class "Default")
      (node (ref "B1") (pin "AB4") (pinfunction "IO_294_AB4") (pintype "passive"))
      (node (ref "J140") (pin "1") (pinfunction "1_1") (pintype "passive"))
    )
    (net (code "141") (name "Net-(B1-IO_295)") (class "Default")
      (node (ref "B1") (pin "AB5") (pinfunction "IO_295_AB5") (pintype "passive"))
      (node (ref "J141") (pin "1") (pinfunction "1_1") (pintype "passive"))
    )
    (net (code "142") (name "Net-(B1-IO_296)") (class "Default")
      (node (ref "B1") (pin "AB6") (pinfunction "IO_296_AB6") (pintype "passive"))
      (node (ref "J142") (pin "1") (pinfunction "1_1") (pintype "passive"))
    )
    (net (code "143") (name "Net-(B1-IO_297)") (class "Default")
      (node (ref "B1") (pin "AB7") (pinfunction "IO_297_AB7") (pintype "passive"))
      (node (ref "J143") (pin "1") (pinfunction "1_1") (pintype "passive"))
    )
    (net (code "144") (name "Net-(B1-IO_298)") (class "Default")
      (node (ref "B1") (pin "AB8") (pinfunction "IO_298_AB8") (pintype "passive"))
      (node (ref "J144") (pin "1") (pinfunction "1_1") (pintype "passive"))
    )
    (net (code "145") (name "Net-(B1-IO_299)") (class "Default")
      (node (ref "B1") (pin "AB9") (pinfunction "IO_299_AB9") (pintype "passive"))
      (node (ref "J145") (pin "1") (pinfunction "1_1") (pintype "passive"))
    )
    (net (code "146") (name "Net-(B1-IO_300)") (class "Default")
      (node (ref "B1") (pin "AB10") (pinfunction "IO_300_AB10") (pintype "passive"))
      (node (ref "J146") (pin "1") (pinfunction "1_1") (pintype "passive"))
    )
    (net (code "147") (name "Net-(B1-IO_301)") (class "Default")
      (node (ref "B1") (pin "AB13") (pinfunction "IO_301_AB13") (pintype "passive"))
      (node (ref "J149") (pin "1") (pinfunction "1_1") (pintype "passive"))
    )
    (net (code "148") (name "Net-(B1-IO_302)") (class "Default")
      (node (ref "B1") (pin "AB14") (pinfunction "IO_302_AB14") (pintype "passive"))
      (node (ref "J150") (pin "1") (pinfunction "1_1") (pintype "passive"))
    )
    (net (code "149") (name "Net-(B1-IO_303)") (class "Default")
      (node (ref "B1") (pin "AB15") (pinfunction "IO_303_AB15") (pintype "passive"))
      (node (ref "J151") (pin "1") (pinfunction "1_1") (pintype "passive"))
    )
    (net (code "150") (name "Net-(B1-IO_304)") (class "Default")
      (node (ref "B1") (pin "AB16") (pinfunction "IO_304_AB16") (pintype "passive"))
      (node (ref "J152") (pin "1") (pinfunction "1_1") (pintype "passive"))
    )
    (net (code "151") (name "Net-(B1-IO_305)") (class "Default")
      (node (ref "B1") (pin "AB17") (pinfunction "IO_305_AB17") (pintype "passive"))
      (node (ref "J153") (pin "1") (pinfunction "1_1") (pintype "passive"))
    )
    (net (code "152") (name "Net-(B1-IO_306)") (class "Default")
      (node (ref "B1") (pin "AB18") (pinfunction "IO_306_AB18") (pintype "passive"))
      (node (ref "J154") (pin "1") (pinfunction "1_1") (pintype "passive"))
    )
    (net (code "153") (name "Net-(B1-IO_307)") (class "Default")
      (node (ref "B1") (pin "AB19") (pinfunction "IO_307_AB19") (pintype "passive"))
      (node (ref "J155") (pin "1") (pinfunction "1_1") (pintype "passive"))
    )
    (net (code "154") (name "Net-(B1-IO_308)") (class "Default")
      (node (ref "B1") (pin "AB20") (pinfunction "IO_308_AB20") (pintype "passive"))
      (node (ref "J156") (pin "1") (pinfunction "1_1") (pintype "passive"))
    )
    (net (code "155") (name "Net-(B1-TCK)") (class "Default")
      (node (ref "B1") (pin "L2") (pinfunction "TCK_L2") (pintype "passive"))
      (node (ref "J137") (pin "1") (pinfunction "1_1") (pintype "passive"))
    )
    (net (code "156") (name "Net-(B1-TMS)") (class "Default")
      (node (ref "B1") (pin "L1") (pinfunction "TMS_L1") (pintype "passive"))
      (node (ref "J135") (pin "1") (pinfunction "1_1") (pintype "passive"))
    )
    (net (code "157") (name "Net-(B1-VCCIO3_4)") (class "Default")
      (node (ref "B1") (pin "AB2") (pinfunction "VCCIO3_4_AB2") (pintype "passive"))
      (node (ref "J138") (pin "1") (pinfunction "1_1") (pintype "passive"))
    )
    (net (code "158") (name "Net-(B1-VCCIO4_4)") (class "Default")
      (node (ref "B1") (pin "AB21") (pinfunction "VCCIO4_4_AB21") (pintype "passive"))
      (node (ref "J158") (pin "1") (pinfunction "1_1") (pintype "passive"))
    )
    (net (code "159") (name "Net-(B1-VCCIO7_1)") (class "Default")
      (node (ref "B1") (pin "A21") (pinfunction "VCCIO7_1_A21") (pintype "passive"))
      (node (ref "J23") (pin "1") (pinfunction "1_1") (pintype "passive"))
    )
    (net (code "160") (name "Net-(B1-VCCIO8_1)") (class "Default")
      (node (ref "B1") (pin "A2") (pinfunction "VCCIO8_1_A2") (pintype "passive"))
      (node (ref "J3") (pin "1") (pinfunction "1_1") (pintype "passive"))
    )
    (net (code "161") (name "unconnected-(B1-AB2-PadG4)") (class "Default")
      (node (ref "B1") (pin "G4") (pinfunction "AB2_G4") (pintype "passive"))
    )
    (net (code "162") (name "unconnected-(B1-CONF_DONE-PadM18)") (class "Default")
      (node (ref "B1") (pin "M18") (pinfunction "CONF_DONE_M18") (pintype "passive"))
    )
    (net (code "163") (name "unconnected-(B1-GNDA1-PadU5)") (class "Default")
      (node (ref "B1") (pin "U5") (pinfunction "GNDA1_U5") (pintype "passive"))
    )
    (net (code "164") (name "unconnected-(B1-GNDA2-PadE18)") (class "Default")
      (node (ref "B1") (pin "E18") (pinfunction "GNDA2_E18") (pintype "passive"))
    )
    (net (code "165") (name "unconnected-(B1-GNDA3-PadF5)") (class "Default")
      (node (ref "B1") (pin "F5") (pinfunction "GNDA3_F5") (pintype "passive"))
    )
    (net (code "166") (name "unconnected-(B1-GNDA4-PadV18)") (class "Default")
      (node (ref "B1") (pin "V18") (pinfunction "GNDA4_V18") (pintype "passive"))
    )
    (net (code "167") (name "unconnected-(B1-GND_3-PadC5)") (class "Default")
      (node (ref "B1") (pin "C5") (pinfunction "GND_3_C5") (pintype "passive"))
    )
    (net (code "168") (name "unconnected-(B1-GND_4-PadC9)") (class "Default")
      (node (ref "B1") (pin "C9") (pinfunction "GND_4_C9") (pintype "passive"))
    )
    (net (code "169") (name "unconnected-(B1-GND_5-PadC11)") (class "Default")
      (node (ref "B1") (pin "C11") (pinfunction "GND_5_C11") (pintype "passive"))
    )
    (net (code "170") (name "unconnected-(B1-GND_6-PadC12)") (class "Default")
      (node (ref "B1") (pin "C12") (pinfunction "GND_6_C12") (pintype "passive"))
    )
    (net (code "171") (name "unconnected-(B1-GND_7-PadC14)") (class "Default")
      (node (ref "B1") (pin "C14") (pinfunction "GND_7_C14") (pintype "passive"))
    )
    (net (code "172") (name "unconnected-(B1-GND_8-PadC16)") (class "Default")
      (node (ref "B1") (pin "C16") (pinfunction "GND_8_C16") (pintype "passive"))
    )
    (net (code "173") (name "unconnected-(B1-GND_9-PadD3)") (class "Default")
      (node (ref "B1") (pin "D3") (pinfunction "GND_9_D3") (pintype "passive"))
    )
    (net (code "174") (name "unconnected-(B1-GND_10-PadE20)") (class "Default")
      (node (ref "B1") (pin "E20") (pinfunction "GND_10_E20") (pintype "passive"))
    )
    (net (code "175") (name "unconnected-(B1-GND_11-PadF3)") (class "Default")
      (node (ref "B1") (pin "F3") (pinfunction "GND_11_F3") (pintype "passive"))
    )
    (net (code "176") (name "unconnected-(B1-GND_12-PadF12)") (class "Default")
      (node (ref "B1") (pin "F12") (pinfunction "GND_12_F12") (pintype "passive"))
    )
    (net (code "177") (name "unconnected-(B1-GND_14-PadG20)") (class "Default")
      (node (ref "B1") (pin "G20") (pinfunction "GND_14_G20") (pintype "passive"))
    )
    (net (code "178") (name "unconnected-(B1-GND_15-PadH8)") (class "Default")
      (node (ref "B1") (pin "H8") (pinfunction "GND_15_H8") (pintype "passive"))
    )
    (net (code "179") (name "unconnected-(B1-GND_16-PadH10)") (class "Default")
      (node (ref "B1") (pin "H10") (pinfunction "GND_16_H10") (pintype "passive"))
    )
    (net (code "180") (name "unconnected-(B1-GND_17-PadH12)") (class "Default")
      (node (ref "B1") (pin "H12") (pinfunction "GND_17_H12") (pintype "passive"))
    )
    (net (code "181") (name "unconnected-(B1-GND_18-PadH13)") (class "Default")
      (node (ref "B1") (pin "H13") (pinfunction "GND_18_H13") (pintype "passive"))
    )
    (net (code "182") (name "unconnected-(B1-GND_19-PadH14)") (class "Default")
      (node (ref "B1") (pin "H14") (pinfunction "GND_19_H14") (pintype "passive"))
    )
    (net (code "183") (name "unconnected-(B1-GND_20-PadJ9)") (class "Default")
      (node (ref "B1") (pin "J9") (pinfunction "GND_20_J9") (pintype "passive"))
    )
    (net (code "184") (name "unconnected-(B1-GND_21-PadJ15)") (class "Default")
      (node (ref "B1") (pin "J15") (pinfunction "GND_21_J15") (pintype "passive"))
    )
    (net (code "185") (name "unconnected-(B1-GND_22-PadK3)") (class "Default")
      (node (ref "B1") (pin "K3") (pinfunction "GND_22_K3") (pintype "passive"))
    )
    (net (code "186") (name "unconnected-(B1-GND_23-PadK10)") (class "Default")
      (node (ref "B1") (pin "K10") (pinfunction "GND_23_K10") (pintype "passive"))
    )
    (net (code "187") (name "unconnected-(B1-GND_24-PadK11)") (class "Default")
      (node (ref "B1") (pin "K11") (pinfunction "GND_24_K11") (pintype "passive"))
    )
    (net (code "188") (name "unconnected-(B1-GND_25-PadK12)") (class "Default")
      (node (ref "B1") (pin "K12") (pinfunction "GND_25_K12") (pintype "passive"))
    )
    (net (code "189") (name "unconnected-(B1-GND_26-PadK13)") (class "Default")
      (node (ref "B1") (pin "K13") (pinfunction "GND_26_K13") (pintype "passive"))
    )
    (net (code "190") (name "unconnected-(B1-GND_27-PadK16)") (class "Default")
      (node (ref "B1") (pin "K16") (pinfunction "GND_27_K16") (pintype "passive"))
    )
    (net (code "191") (name "unconnected-(B1-GND_28-PadL8)") (class "Default")
      (node (ref "B1") (pin "L8") (pinfunction "GND_28_L8") (pintype "passive"))
    )
    (net (code "192") (name "unconnected-(B1-GND_29-PadL10)") (class "Default")
      (node (ref "B1") (pin "L10") (pinfunction "GND_29_L10") (pintype "passive"))
    )
    (net (code "193") (name "unconnected-(B1-GND_30-PadL11)") (class "Default")
      (node (ref "B1") (pin "L11") (pinfunction "GND_30_L11") (pintype "passive"))
    )
    (net (code "194") (name "unconnected-(B1-GND_31-PadL12)") (class "Default")
      (node (ref "B1") (pin "L12") (pinfunction "GND_31_L12") (pintype "passive"))
    )
    (net (code "195") (name "unconnected-(B1-GND_32-PadL13)") (class "Default")
      (node (ref "B1") (pin "L13") (pinfunction "GND_32_L13") (pintype "passive"))
    )
    (net (code "196") (name "unconnected-(B1-GND_33-PadL15)") (class "Default")
      (node (ref "B1") (pin "L15") (pinfunction "GND_33_L15") (pintype "passive"))
    )
    (net (code "197") (name "unconnected-(B1-GND_34-PadL20)") (class "Default")
      (node (ref "B1") (pin "L20") (pinfunction "GND_34_L20") (pintype "passive"))
    )
    (net (code "198") (name "unconnected-(B1-GND_35-PadM7)") (class "Default")
      (node (ref "B1") (pin "M7") (pinfunction "GND_35_M7") (pintype "passive"))
    )
    (net (code "199") (name "unconnected-(B1-GND_36-PadM10)") (class "Default")
      (node (ref "B1") (pin "M10") (pinfunction "GND_36_M10") (pintype "passive"))
    )
    (net (code "200") (name "unconnected-(B1-GND_37-PadM11)") (class "Default")
      (node (ref "B1") (pin "M11") (pinfunction "GND_37_M11") (pintype "passive"))
    )
    (net (code "201") (name "unconnected-(B1-GND_38-PadM12)") (class "Default")
      (node (ref "B1") (pin "M12") (pinfunction "GND_38_M12") (pintype "passive"))
    )
    (net (code "202") (name "unconnected-(B1-GND_39-PadM13)") (class "Default")
      (node (ref "B1") (pin "M13") (pinfunction "GND_39_M13") (pintype "passive"))
    )
    (net (code "203") (name "unconnected-(B1-GND_40-PadN3)") (class "Default")
      (node (ref "B1") (pin "N3") (pinfunction "GND_40_N3") (pintype "passive"))
    )
    (net (code "204") (name "unconnected-(B1-GND_41-PadN8)") (class "Default")
      (node (ref "B1") (pin "N8") (pinfunction "GND_41_N8") (pintype "passive"))
    )
    (net (code "205") (name "unconnected-(B1-GND_42-PadN10)") (class "Default")
      (node (ref "B1") (pin "N10") (pinfunction "GND_42_N10") (pintype "passive"))
    )
    (net (code "206") (name "unconnected-(B1-GND_43-PadN11)") (class "Default")
      (node (ref "B1") (pin "N11") (pinfunction "GND_43_N11") (pintype "passive"))
    )
    (net (code "207") (name "unconnected-(B1-GND_44-PadN12)") (class "Default")
      (node (ref "B1") (pin "N12") (pinfunction "GND_44_N12") (pintype "passive"))
    )
    (net (code "208") (name "unconnected-(B1-GND_45-PadN13)") (class "Default")
      (node (ref "B1") (pin "N13") (pinfunction "GND_45_N13") (pintype "passive"))
    )
    (net (code "209") (name "unconnected-(B1-GND_46-PadN15)") (class "Default")
      (node (ref "B1") (pin "N15") (pinfunction "GND_46_N15") (pintype "passive"))
    )
    (net (code "210") (name "unconnected-(B1-GND_47-PadP8)") (class "Default")
      (node (ref "B1") (pin "P8") (pinfunction "GND_47_P8") (pintype "passive"))
    )
    (net (code "211") (name "unconnected-(B1-GND_48-PadP16)") (class "Default")
      (node (ref "B1") (pin "P16") (pinfunction "GND_48_P16") (pintype "passive"))
    )
    (net (code "212") (name "unconnected-(B1-GND_49-PadP19)") (class "Default")
      (node (ref "B1") (pin "P19") (pinfunction "GND_49_P19") (pintype "passive"))
    )
    (net (code "213") (name "unconnected-(B1-GND_50-PadR7)") (class "Default")
      (node (ref "B1") (pin "R7") (pinfunction "GND_50_R7") (pintype "passive"))
    )
    (net (code "214") (name "unconnected-(B1-GND_51-PadR9)") (class "Default")
      (node (ref "B1") (pin "R9") (pinfunction "GND_51_R9") (pintype "passive"))
    )
    (net (code "215") (name "unconnected-(B1-GND_52-PadR11)") (class "Default")
      (node (ref "B1") (pin "R11") (pinfunction "GND_52_R11") (pintype "passive"))
    )
    (net (code "216") (name "unconnected-(B1-GND_53-PadR13)") (class "Default")
      (node (ref "B1") (pin "R13") (pinfunction "GND_53_R13") (pintype "passive"))
    )
    (net (code "217") (name "unconnected-(B1-GND_54-PadT8)") (class "Default")
      (node (ref "B1") (pin "T8") (pinfunction "GND_54_T8") (pintype "passive"))
    )
    (net (code "218") (name "unconnected-(B1-GND_55-PadT12)") (class "Default")
      (node (ref "B1") (pin "T12") (pinfunction "GND_55_T12") (pintype "passive"))
    )
    (net (code "219") (name "unconnected-(B1-GND_56-PadU3)") (class "Default")
      (node (ref "B1") (pin "U3") (pinfunction "GND_56_U3") (pintype "passive"))
    )
    (net (code "220") (name "unconnected-(B1-GND_57-PadV20)") (class "Default")
      (node (ref "B1") (pin "V20") (pinfunction "GND_57_V20") (pintype "passive"))
    )
    (net (code "221") (name "unconnected-(B1-GND_58-PadW3)") (class "Default")
      (node (ref "B1") (pin "W3") (pinfunction "GND_58_W3") (pintype "passive"))
    )
    (net (code "222") (name "unconnected-(B1-GND_59-PadY5)") (class "Default")
      (node (ref "B1") (pin "Y5") (pinfunction "GND_59_Y5") (pintype "passive"))
    )
    (net (code "223") (name "unconnected-(B1-GND_60-PadY9)") (class "Default")
      (node (ref "B1") (pin "Y9") (pinfunction "GND_60_Y9") (pintype "passive"))
    )
    (net (code "224") (name "unconnected-(B1-GND_61-PadY11)") (class "Default")
      (node (ref "B1") (pin "Y11") (pinfunction "GND_61_Y11") (pintype "passive"))
    )
    (net (code "225") (name "unconnected-(B1-GND_62-PadY12)") (class "Default")
      (node (ref "B1") (pin "Y12") (pinfunction "GND_62_Y12") (pintype "passive"))
    )
    (net (code "226") (name "unconnected-(B1-GND_63-PadY16)") (class "Default")
      (node (ref "B1") (pin "Y16") (pinfunction "GND_63_Y16") (pintype "passive"))
    )
    (net (code "227") (name "unconnected-(B1-GND_64-PadY18)") (class "Default")
      (node (ref "B1") (pin "Y18") (pinfunction "GND_64_Y18") (pintype "passive"))
    )
    (net (code "228") (name "unconnected-(B1-GND_65-PadY20)") (class "Default")
      (node (ref "B1") (pin "Y20") (pinfunction "GND_65_Y20") (pintype "passive"))
    )
    (net (code "229") (name "unconnected-(B1-IO_39-PadC3)") (class "Default")
      (node (ref "B1") (pin "C3") (pinfunction "IO_39_C3") (pintype "passive"))
    )
    (net (code "230") (name "unconnected-(B1-IO_40-PadC4)") (class "Default")
      (node (ref "B1") (pin "C4") (pinfunction "IO_40_C4") (pintype "passive"))
    )
    (net (code "231") (name "unconnected-(B1-IO_41-PadC6)") (class "Default")
      (node (ref "B1") (pin "C6") (pinfunction "IO_41_C6") (pintype "passive"))
    )
    (net (code "232") (name "unconnected-(B1-IO_42-PadC7)") (class "Default")
      (node (ref "B1") (pin "C7") (pinfunction "IO_42_C7") (pintype "passive"))
    )
    (net (code "233") (name "unconnected-(B1-IO_43-PadC8)") (class "Default")
      (node (ref "B1") (pin "C8") (pinfunction "IO_43_C8") (pintype "passive"))
    )
    (net (code "234") (name "unconnected-(B1-IO_44-PadC10)") (class "Default")
      (node (ref "B1") (pin "C10") (pinfunction "IO_44_C10") (pintype "passive"))
    )
    (net (code "235") (name "unconnected-(B1-IO_45-PadC13)") (class "Default")
      (node (ref "B1") (pin "C13") (pinfunction "IO_45_C13") (pintype "passive"))
    )
    (net (code "236") (name "unconnected-(B1-IO_46-PadC15)") (class "Default")
      (node (ref "B1") (pin "C15") (pinfunction "IO_46_C15") (pintype "passive"))
    )
    (net (code "237") (name "unconnected-(B1-IO_47-PadC17)") (class "Default")
      (node (ref "B1") (pin "C17") (pinfunction "IO_47_C17") (pintype "passive"))
    )
    (net (code "238") (name "unconnected-(B1-IO_48-PadC18)") (class "Default")
      (node (ref "B1") (pin "C18") (pinfunction "IO_48_C18") (pintype "passive"))
    )
    (net (code "239") (name "unconnected-(B1-IO_49-PadC19)") (class "Default")
      (node (ref "B1") (pin "C19") (pinfunction "IO_49_C19") (pintype "passive"))
    )
    (net (code "240") (name "unconnected-(B1-IO_50-PadC20)") (class "Default")
      (node (ref "B1") (pin "C20") (pinfunction "IO_50_C20") (pintype "passive"))
    )
    (net (code "241") (name "unconnected-(B1-IO_55-PadD6)") (class "Default")
      (node (ref "B1") (pin "D6") (pinfunction "IO_55_D6") (pintype "passive"))
    )
    (net (code "242") (name "unconnected-(B1-IO_56-PadD7)") (class "Default")
      (node (ref "B1") (pin "D7") (pinfunction "IO_56_D7") (pintype "passive"))
    )
    (net (code "243") (name "unconnected-(B1-IO_57-PadD8)") (class "Default")
      (node (ref "B1") (pin "D8") (pinfunction "IO_57_D8") (pintype "passive"))
    )
    (net (code "244") (name "unconnected-(B1-IO_58-PadD10)") (class "Default")
      (node (ref "B1") (pin "D10") (pinfunction "IO_58_D10") (pintype "passive"))
    )
    (net (code "245") (name "unconnected-(B1-IO_59-PadD13)") (class "Default")
      (node (ref "B1") (pin "D13") (pinfunction "IO_59_D13") (pintype "passive"))
    )
    (net (code "246") (name "unconnected-(B1-IO_60-PadD15)") (class "Default")
      (node (ref "B1") (pin "D15") (pinfunction "IO_60_D15") (pintype "passive"))
    )
    (net (code "247") (name "unconnected-(B1-IO_61-PadD17)") (class "Default")
      (node (ref "B1") (pin "D17") (pinfunction "IO_61_D17") (pintype "passive"))
    )
    (net (code "248") (name "unconnected-(B1-IO_62-PadD18)") (class "Default")
      (node (ref "B1") (pin "D18") (pinfunction "IO_62_D18") (pintype "passive"))
    )
    (net (code "249") (name "unconnected-(B1-IO_63-PadD19)") (class "Default")
      (node (ref "B1") (pin "D19") (pinfunction "IO_63_D19") (pintype "passive"))
    )
    (net (code "250") (name "unconnected-(B1-IO_64-PadD20)") (class "Default")
      (node (ref "B1") (pin "D20") (pinfunction "IO_64_D20") (pintype "passive"))
    )
    (net (code "251") (name "unconnected-(B1-IO_69-PadE3)") (class "Default")
      (node (ref "B1") (pin "E3") (pinfunction "IO_69_E3") (pintype "passive"))
    )
    (net (code "252") (name "unconnected-(B1-IO_70-PadE4)") (class "Default")
      (node (ref "B1") (pin "E4") (pinfunction "IO_70_E4") (pintype "passive"))
    )
    (net (code "253") (name "unconnected-(B1-IO_71-PadE5)") (class "Default")
      (node (ref "B1") (pin "E5") (pinfunction "IO_71_E5") (pintype "passive"))
    )
    (net (code "254") (name "unconnected-(B1-IO_72-PadE6)") (class "Default")
      (node (ref "B1") (pin "E6") (pinfunction "IO_72_E6") (pintype "passive"))
    )
    (net (code "255") (name "unconnected-(B1-IO_73-PadE7)") (class "Default")
      (node (ref "B1") (pin "E7") (pinfunction "IO_73_E7") (pintype "passive"))
    )
    (net (code "256") (name "unconnected-(B1-IO_74-PadE8)") (class "Default")
      (node (ref "B1") (pin "E8") (pinfunction "IO_74_E8") (pintype "passive"))
    )
    (net (code "257") (name "unconnected-(B1-IO_75-PadE9)") (class "Default")
      (node (ref "B1") (pin "E9") (pinfunction "IO_75_E9") (pintype "passive"))
    )
    (net (code "258") (name "unconnected-(B1-IO_76-PadE10)") (class "Default")
      (node (ref "B1") (pin "E10") (pinfunction "IO_76_E10") (pintype "passive"))
    )
    (net (code "259") (name "unconnected-(B1-IO_77-PadE11)") (class "Default")
      (node (ref "B1") (pin "E11") (pinfunction "IO_77_E11") (pintype "passive"))
    )
    (net (code "260") (name "unconnected-(B1-IO_78-PadE12)") (class "Default")
      (node (ref "B1") (pin "E12") (pinfunction "IO_78_E12") (pintype "passive"))
    )
    (net (code "261") (name "unconnected-(B1-IO_79-PadE13)") (class "Default")
      (node (ref "B1") (pin "E13") (pinfunction "IO_79_E13") (pintype "passive"))
    )
    (net (code "262") (name "unconnected-(B1-IO_80-PadE14)") (class "Default")
      (node (ref "B1") (pin "E14") (pinfunction "IO_80_E14") (pintype "passive"))
    )
    (net (code "263") (name "unconnected-(B1-IO_81-PadE15)") (class "Default")
      (node (ref "B1") (pin "E15") (pinfunction "IO_81_E15") (pintype "passive"))
    )
    (net (code "264") (name "unconnected-(B1-IO_82-PadE16)") (class "Default")
      (node (ref "B1") (pin "E16") (pinfunction "IO_82_E16") (pintype "passive"))
    )
    (net (code "265") (name "unconnected-(B1-IO_87-PadF7)") (class "Default")
      (node (ref "B1") (pin "F7") (pinfunction "IO_87_F7") (pintype "passive"))
    )
    (net (code "266") (name "unconnected-(B1-IO_88-PadF8)") (class "Default")
      (node (ref "B1") (pin "F8") (pinfunction "IO_88_F8") (pintype "passive"))
    )
    (net (code "267") (name "unconnected-(B1-IO_89-PadF9)") (class "Default")
      (node (ref "B1") (pin "F9") (pinfunction "IO_89_F9") (pintype "passive"))
    )
    (net (code "268") (name "unconnected-(B1-IO_90-PadF10)") (class "Default")
      (node (ref "B1") (pin "F10") (pinfunction "IO_90_F10") (pintype "passive"))
    )
    (net (code "269") (name "unconnected-(B1-IO_91-PadF11)") (class "Default")
      (node (ref "B1") (pin "F11") (pinfunction "IO_91_F11") (pintype "passive"))
    )
    (net (code "270") (name "unconnected-(B1-IO_92-PadF13)") (class "Default")
      (node (ref "B1") (pin "F13") (pinfunction "IO_92_F13") (pintype "passive"))
    )
    (net (code "271") (name "unconnected-(B1-IO_93-PadF14)") (class "Default")
      (node (ref "B1") (pin "F14") (pinfunction "IO_93_F14") (pintype "passive"))
    )
    (net (code "272") (name "unconnected-(B1-IO_94-PadF15)") (class "Default")
      (node (ref "B1") (pin "F15") (pinfunction "IO_94_F15") (pintype "passive"))
    )
    (net (code "273") (name "unconnected-(B1-IO_95-PadF16)") (class "Default")
      (node (ref "B1") (pin "F16") (pinfunction "IO_95_F16") (pintype "passive"))
    )
    (net (code "274") (name "unconnected-(B1-IO_96-PadF17)") (class "Default")
      (node (ref "B1") (pin "F17") (pinfunction "IO_96_F17") (pintype "passive"))
    )
    (net (code "275") (name "unconnected-(B1-IO_97-PadF19)") (class "Default")
      (node (ref "B1") (pin "F19") (pinfunction "IO_97_F19") (pintype "passive"))
    )
    (net (code "276") (name "unconnected-(B1-IO_98-PadF20)") (class "Default")
      (node (ref "B1") (pin "F20") (pinfunction "IO_98_F20") (pintype "passive"))
    )
    (net (code "277") (name "unconnected-(B1-IO_101-PadG3)") (class "Default")
      (node (ref "B1") (pin "G3") (pinfunction "IO_101_G3") (pintype "passive"))
    )
    (net (code "278") (name "unconnected-(B1-IO_102-PadG5)") (class "Default")
      (node (ref "B1") (pin "G5") (pinfunction "IO_102_G5") (pintype "passive"))
    )
    (net (code "279") (name "unconnected-(B1-IO_103-PadG7)") (class "Default")
      (node (ref "B1") (pin "G7") (pinfunction "IO_103_G7") (pintype "passive"))
    )
    (net (code "280") (name "unconnected-(B1-IO_104-PadG8)") (class "Default")
      (node (ref "B1") (pin "G8") (pinfunction "IO_104_G8") (pintype "passive"))
    )
    (net (code "281") (name "unconnected-(B1-IO_105-PadG9)") (class "Default")
      (node (ref "B1") (pin "G9") (pinfunction "IO_105_G9") (pintype "passive"))
    )
    (net (code "282") (name "unconnected-(B1-IO_106-PadG10)") (class "Default")
      (node (ref "B1") (pin "G10") (pinfunction "IO_106_G10") (pintype "passive"))
    )
    (net (code "283") (name "unconnected-(B1-IO_107-PadG11)") (class "Default")
      (node (ref "B1") (pin "G11") (pinfunction "IO_107_G11") (pintype "passive"))
    )
    (net (code "284") (name "unconnected-(B1-IO_108-PadG13)") (class "Default")
      (node (ref "B1") (pin "G13") (pinfunction "IO_108_G13") (pintype "passive"))
    )
    (net (code "285") (name "unconnected-(B1-IO_109-PadG14)") (class "Default")
      (node (ref "B1") (pin "G14") (pinfunction "IO_109_G14") (pintype "passive"))
    )
    (net (code "286") (name "unconnected-(B1-IO_110-PadG15)") (class "Default")
      (node (ref "B1") (pin "G15") (pinfunction "IO_110_G15") (pintype "passive"))
    )
    (net (code "287") (name "unconnected-(B1-IO_111-PadG16)") (class "Default")
      (node (ref "B1") (pin "G16") (pinfunction "IO_111_G16") (pintype "passive"))
    )
    (net (code "288") (name "unconnected-(B1-IO_112-PadG17)") (class "Default")
      (node (ref "B1") (pin "G17") (pinfunction "IO_112_G17") (pintype "passive"))
    )
    (net (code "289") (name "unconnected-(B1-IO_113-PadG18)") (class "Default")
      (node (ref "B1") (pin "G18") (pinfunction "IO_113_G18") (pintype "passive"))
    )
    (net (code "290") (name "unconnected-(B1-IO_116-PadH3)") (class "Default")
      (node (ref "B1") (pin "H3") (pinfunction "IO_116_H3") (pintype "passive"))
    )
    (net (code "291") (name "unconnected-(B1-IO_117-PadH4)") (class "Default")
      (node (ref "B1") (pin "H4") (pinfunction "IO_117_H4") (pintype "passive"))
    )
    (net (code "292") (name "unconnected-(B1-IO_118-PadH5)") (class "Default")
      (node (ref "B1") (pin "H5") (pinfunction "IO_118_H5") (pintype "passive"))
    )
    (net (code "293") (name "unconnected-(B1-IO_119-PadH6)") (class "Default")
      (node (ref "B1") (pin "H6") (pinfunction "IO_119_H6") (pintype "passive"))
    )
    (net (code "294") (name "unconnected-(B1-IO_120-PadH7)") (class "Default")
      (node (ref "B1") (pin "H7") (pinfunction "IO_120_H7") (pintype "passive"))
    )
    (net (code "295") (name "unconnected-(B1-IO_121-PadH16)") (class "Default")
      (node (ref "B1") (pin "H16") (pinfunction "IO_121_H16") (pintype "passive"))
    )
    (net (code "296") (name "unconnected-(B1-IO_122-PadH17)") (class "Default")
      (node (ref "B1") (pin "H17") (pinfunction "IO_122_H17") (pintype "passive"))
    )
    (net (code "297") (name "unconnected-(B1-IO_123-PadH18)") (class "Default")
      (node (ref "B1") (pin "H18") (pinfunction "IO_123_H18") (pintype "passive"))
    )
    (net (code "298") (name "unconnected-(B1-IO_124-PadH19)") (class "Default")
      (node (ref "B1") (pin "H19") (pinfunction "IO_124_H19") (pintype "passive"))
    )
    (net (code "299") (name "unconnected-(B1-IO_125-PadH20)") (class "Default")
      (node (ref "B1") (pin "H20") (pinfunction "IO_125_H20") (pintype "passive"))
    )
    (net (code "300") (name "unconnected-(B1-IO_130-PadJ3)") (class "Default")
      (node (ref "B1") (pin "J3") (pinfunction "IO_130_J3") (pintype "passive"))
    )
    (net (code "301") (name "unconnected-(B1-IO_131-PadJ4)") (class "Default")
      (node (ref "B1") (pin "J4") (pinfunction "IO_131_J4") (pintype "passive"))
    )
    (net (code "302") (name "unconnected-(B1-IO_132-PadJ5)") (class "Default")
      (node (ref "B1") (pin "J5") (pinfunction "IO_132_J5") (pintype "passive"))
    )
    (net (code "303") (name "unconnected-(B1-IO_133-PadJ6)") (class "Default")
      (node (ref "B1") (pin "J6") (pinfunction "IO_133_J6") (pintype "passive"))
    )
    (net (code "304") (name "unconnected-(B1-IO_134-PadJ7)") (class "Default")
      (node (ref "B1") (pin "J7") (pinfunction "IO_134_J7") (pintype "passive"))
    )
    (net (code "305") (name "unconnected-(B1-IO_135-PadJ17)") (class "Default")
      (node (ref "B1") (pin "J17") (pinfunction "IO_135_J17") (pintype "passive"))
    )
    (net (code "306") (name "unconnected-(B1-IO_136-PadJ18)") (class "Default")
      (node (ref "B1") (pin "J18") (pinfunction "IO_136_J18") (pintype "passive"))
    )
    (net (code "307") (name "unconnected-(B1-IO_137-PadJ19)") (class "Default")
      (node (ref "B1") (pin "J19") (pinfunction "IO_137_J19") (pintype "passive"))
    )
    (net (code "308") (name "unconnected-(B1-IO_138-PadJ20)") (class "Default")
      (node (ref "B1") (pin "J20") (pinfunction "IO_138_J20") (pintype "passive"))
    )
    (net (code "309") (name "unconnected-(B1-IO_142-PadK7)") (class "Default")
      (node (ref "B1") (pin "K7") (pinfunction "IO_142_K7") (pintype "passive"))
    )
    (net (code "310") (name "unconnected-(B1-IO_143-PadK17)") (class "Default")
      (node (ref "B1") (pin "K17") (pinfunction "IO_143_K17") (pintype "passive"))
    )
    (net (code "311") (name "unconnected-(B1-IO_144-PadK18)") (class "Default")
      (node (ref "B1") (pin "K18") (pinfunction "IO_144_K18") (pintype "passive"))
    )
    (net (code "312") (name "unconnected-(B1-IO_145-PadK19)") (class "Default")
      (node (ref "B1") (pin "K19") (pinfunction "IO_145_K19") (pintype "passive"))
    )
    (net (code "313") (name "unconnected-(B1-IO_148-PadL6)") (class "Default")
      (node (ref "B1") (pin "L6") (pinfunction "IO_148_L6") (pintype "passive"))
    )
    (net (code "314") (name "unconnected-(B1-IO_153-PadM3)") (class "Default")
      (node (ref "B1") (pin "M3") (pinfunction "IO_153_M3") (pintype "passive"))
    )
    (net (code "315") (name "unconnected-(B1-IO_154-PadM4)") (class "Default")
      (node (ref "B1") (pin "M4") (pinfunction "IO_154_M4") (pintype "passive"))
    )
    (net (code "316") (name "unconnected-(B1-IO_155-PadM5)") (class "Default")
      (node (ref "B1") (pin "M5") (pinfunction "IO_155_M5") (pintype "passive"))
    )
    (net (code "317") (name "unconnected-(B1-IO_156-PadM6)") (class "Default")
      (node (ref "B1") (pin "M6") (pinfunction "IO_156_M6") (pintype "passive"))
    )
    (net (code "318") (name "unconnected-(B1-IO_157-PadM16)") (class "Default")
      (node (ref "B1") (pin "M16") (pinfunction "IO_157_M16") (pintype "passive"))
    )
    (net (code "319") (name "unconnected-(B1-IO_158-PadM19)") (class "Default")
      (node (ref "B1") (pin "M19") (pinfunction "IO_158_M19") (pintype "passive"))
    )
    (net (code "320") (name "unconnected-(B1-IO_159-PadM20)") (class "Default")
      (node (ref "B1") (pin "M20") (pinfunction "IO_159_M20") (pintype "passive"))
    )
    (net (code "321") (name "unconnected-(B1-IO_164-PadN5)") (class "Default")
      (node (ref "B1") (pin "N5") (pinfunction "IO_164_N5") (pintype "passive"))
    )
    (net (code "322") (name "unconnected-(B1-IO_165-PadN6)") (class "Default")
      (node (ref "B1") (pin "N6") (pinfunction "IO_165_N6") (pintype "passive"))
    )
    (net (code "323") (name "unconnected-(B1-IO_166-PadN7)") (class "Default")
      (node (ref "B1") (pin "N7") (pinfunction "IO_166_N7") (pintype "passive"))
    )
    (net (code "324") (name "unconnected-(B1-IO_167-PadN16)") (class "Default")
      (node (ref "B1") (pin "N16") (pinfunction "IO_167_N16") (pintype "passive"))
    )
    (net (code "325") (name "unconnected-(B1-IO_168-PadN17)") (class "Default")
      (node (ref "B1") (pin "N17") (pinfunction "IO_168_N17") (pintype "passive"))
    )
    (net (code "326") (name "unconnected-(B1-IO_169-PadN18)") (class "Default")
      (node (ref "B1") (pin "N18") (pinfunction "IO_169_N18") (pintype "passive"))
    )
    (net (code "327") (name "unconnected-(B1-IO_170-PadN19)") (class "Default")
      (node (ref "B1") (pin "N19") (pinfunction "IO_170_N19") (pintype "passive"))
    )
    (net (code "328") (name "unconnected-(B1-IO_171-PadN20)") (class "Default")
      (node (ref "B1") (pin "N20") (pinfunction "IO_171_N20") (pintype "passive"))
    )
    (net (code "329") (name "unconnected-(B1-IO_176-PadP3)") (class "Default")
      (node (ref "B1") (pin "P3") (pinfunction "IO_176_P3") (pintype "passive"))
    )
    (net (code "330") (name "unconnected-(B1-IO_177-PadP4)") (class "Default")
      (node (ref "B1") (pin "P4") (pinfunction "IO_177_P4") (pintype "passive"))
    )
    (net (code "331") (name "unconnected-(B1-IO_178-PadP5)") (class "Default")
      (node (ref "B1") (pin "P5") (pinfunction "IO_178_P5") (pintype "passive"))
    )
    (net (code "332") (name "unconnected-(B1-IO_179-PadP6)") (class "Default")
      (node (ref "B1") (pin "P6") (pinfunction "IO_179_P6") (pintype "passive"))
    )
    (net (code "333") (name "unconnected-(B1-IO_180-PadP7)") (class "Default")
      (node (ref "B1") (pin "P7") (pinfunction "IO_180_P7") (pintype "passive"))
    )
    (net (code "334") (name "unconnected-(B1-IO_181-PadP17)") (class "Default")
      (node (ref "B1") (pin "P17") (pinfunction "IO_181_P17") (pintype "passive"))
    )
    (net (code "335") (name "unconnected-(B1-IO_182-PadP20)") (class "Default")
      (node (ref "B1") (pin "P20") (pinfunction "IO_182_P20") (pintype "passive"))
    )
    (net (code "336") (name "unconnected-(B1-IO_187-PadR3)") (class "Default")
      (node (ref "B1") (pin "R3") (pinfunction "IO_187_R3") (pintype "passive"))
    )
    (net (code "337") (name "unconnected-(B1-IO_188-PadR4)") (class "Default")
      (node (ref "B1") (pin "R4") (pinfunction "IO_188_R4") (pintype "passive"))
    )
    (net (code "338") (name "unconnected-(B1-IO_189-PadR5)") (class "Default")
      (node (ref "B1") (pin "R5") (pinfunction "IO_189_R5") (pintype "passive"))
    )
    (net (code "339") (name "unconnected-(B1-IO_190-PadR6)") (class "Default")
      (node (ref "B1") (pin "R6") (pinfunction "IO_190_R6") (pintype "passive"))
    )
    (net (code "340") (name "unconnected-(B1-IO_191-PadR14)") (class "Default")
      (node (ref "B1") (pin "R14") (pinfunction "IO_191_R14") (pintype "passive"))
    )
    (net (code "341") (name "unconnected-(B1-IO_192-PadR15)") (class "Default")
      (node (ref "B1") (pin "R15") (pinfunction "IO_192_R15") (pintype "passive"))
    )
    (net (code "342") (name "unconnected-(B1-IO_193-PadR16)") (class "Default")
      (node (ref "B1") (pin "R16") (pinfunction "IO_193_R16") (pintype "passive"))
    )
    (net (code "343") (name "unconnected-(B1-IO_194-PadR17)") (class "Default")
      (node (ref "B1") (pin "R17") (pinfunction "IO_194_R17") (pintype "passive"))
    )
    (net (code "344") (name "unconnected-(B1-IO_195-PadR18)") (class "Default")
      (node (ref "B1") (pin "R18") (pinfunction "IO_195_R18") (pintype "passive"))
    )
    (net (code "345") (name "unconnected-(B1-IO_196-PadR19)") (class "Default")
      (node (ref "B1") (pin "R19") (pinfunction "IO_196_R19") (pintype "passive"))
    )
    (net (code "346") (name "unconnected-(B1-IO_197-PadR20)") (class "Default")
      (node (ref "B1") (pin "R20") (pinfunction "IO_197_R20") (pintype "passive"))
    )
    (net (code "347") (name "unconnected-(B1-IO_200-PadT3)") (class "Default")
      (node (ref "B1") (pin "T3") (pinfunction "IO_200_T3") (pintype "passive"))
    )
    (net (code "348") (name "unconnected-(B1-IO_201-PadT4)") (class "Default")
      (node (ref "B1") (pin "T4") (pinfunction "IO_201_T4") (pintype "passive"))
    )
    (net (code "349") (name "unconnected-(B1-IO_202-PadT5)") (class "Default")
      (node (ref "B1") (pin "T5") (pinfunction "IO_202_T5") (pintype "passive"))
    )
    (net (code "350") (name "unconnected-(B1-IO_203-PadT10)") (class "Default")
      (node (ref "B1") (pin "T10") (pinfunction "IO_203_T10") (pintype "passive"))
    )
    (net (code "351") (name "unconnected-(B1-IO_204-PadT11)") (class "Default")
      (node (ref "B1") (pin "T11") (pinfunction "IO_204_T11") (pintype "passive"))
    )
    (net (code "352") (name "unconnected-(B1-IO_205-PadT14)") (class "Default")
      (node (ref "B1") (pin "T14") (pinfunction "IO_205_T14") (pintype "passive"))
    )
    (net (code "353") (name "unconnected-(B1-IO_206-PadT15)") (class "Default")
      (node (ref "B1") (pin "T15") (pinfunction "IO_206_T15") (pintype "passive"))
    )
    (net (code "354") (name "unconnected-(B1-IO_207-PadT16)") (class "Default")
      (node (ref "B1") (pin "T16") (pinfunction "IO_207_T16") (pintype "passive"))
    )
    (net (code "355") (name "unconnected-(B1-IO_208-PadT17)") (class "Default")
      (node (ref "B1") (pin "T17") (pinfunction "IO_208_T17") (pintype "passive"))
    )
    (net (code "356") (name "unconnected-(B1-IO_209-PadT18)") (class "Default")
      (node (ref "B1") (pin "T18") (pinfunction "IO_209_T18") (pintype "passive"))
    )
    (net (code "357") (name "unconnected-(B1-IO_210-PadT19)") (class "Default")
      (node (ref "B1") (pin "T19") (pinfunction "IO_210_T19") (pintype "passive"))
    )
    (net (code "358") (name "unconnected-(B1-IO_211-PadT20)") (class "Default")
      (node (ref "B1") (pin "T20") (pinfunction "IO_211_T20") (pintype "passive"))
    )
    (net (code "359") (name "unconnected-(B1-IO_214-PadU7)") (class "Default")
      (node (ref "B1") (pin "U7") (pinfunction "IO_214_U7") (pintype "passive"))
    )
    (net (code "360") (name "unconnected-(B1-IO_215-PadU8)") (class "Default")
      (node (ref "B1") (pin "U8") (pinfunction "IO_215_U8") (pintype "passive"))
    )
    (net (code "361") (name "unconnected-(B1-IO_216-PadU9)") (class "Default")
      (node (ref "B1") (pin "U9") (pinfunction "IO_216_U9") (pintype "passive"))
    )
    (net (code "362") (name "unconnected-(B1-IO_217-PadU10)") (class "Default")
      (node (ref "B1") (pin "U10") (pinfunction "IO_217_U10") (pintype "passive"))
    )
    (net (code "363") (name "unconnected-(B1-IO_218-PadU11)") (class "Default")
      (node (ref "B1") (pin "U11") (pinfunction "IO_218_U11") (pintype "passive"))
    )
    (net (code "364") (name "unconnected-(B1-IO_219-PadU12)") (class "Default")
      (node (ref "B1") (pin "U12") (pinfunction "IO_219_U12") (pintype "passive"))
    )
    (net (code "365") (name "unconnected-(B1-IO_220-PadU13)") (class "Default")
      (node (ref "B1") (pin "U13") (pinfunction "IO_220_U13") (pintype "passive"))
    )
    (net (code "366") (name "unconnected-(B1-IO_221-PadU14)") (class "Default")
      (node (ref "B1") (pin "U14") (pinfunction "IO_221_U14") (pintype "passive"))
    )
    (net (code "367") (name "unconnected-(B1-IO_222-PadU15)") (class "Default")
      (node (ref "B1") (pin "U15") (pinfunction "IO_222_U15") (pintype "passive"))
    )
    (net (code "368") (name "unconnected-(B1-IO_223-PadU16)") (class "Default")
      (node (ref "B1") (pin "U16") (pinfunction "IO_223_U16") (pintype "passive"))
    )
    (net (code "369") (name "unconnected-(B1-IO_224-PadU17)") (class "Default")
      (node (ref "B1") (pin "U17") (pinfunction "IO_224_U17") (pintype "passive"))
    )
    (net (code "370") (name "unconnected-(B1-IO_225-PadU19)") (class "Default")
      (node (ref "B1") (pin "U19") (pinfunction "IO_225_U19") (pintype "passive"))
    )
    (net (code "371") (name "unconnected-(B1-IO_226-PadU20)") (class "Default")
      (node (ref "B1") (pin "U20") (pinfunction "IO_226_U20") (pintype "passive"))
    )
    (net (code "372") (name "unconnected-(B1-IO_231-PadV3)") (class "Default")
      (node (ref "B1") (pin "V3") (pinfunction "IO_231_V3") (pintype "passive"))
    )
    (net (code "373") (name "unconnected-(B1-IO_232-PadV4)") (class "Default")
      (node (ref "B1") (pin "V4") (pinfunction "IO_232_V4") (pintype "passive"))
    )
    (net (code "374") (name "unconnected-(B1-IO_233-PadV5)") (class "Default")
      (node (ref "B1") (pin "V5") (pinfunction "IO_233_V5") (pintype "passive"))
    )
    (net (code "375") (name "unconnected-(B1-IO_234-PadV6)") (class "Default")
      (node (ref "B1") (pin "V6") (pinfunction "IO_234_V6") (pintype "passive"))
    )
    (net (code "376") (name "unconnected-(B1-IO_235-PadV7)") (class "Default")
      (node (ref "B1") (pin "V7") (pinfunction "IO_235_V7") (pintype "passive"))
    )
    (net (code "377") (name "unconnected-(B1-IO_236-PadV8)") (class "Default")
      (node (ref "B1") (pin "V8") (pinfunction "IO_236_V8") (pintype "passive"))
    )
    (net (code "378") (name "unconnected-(B1-IO_237-PadV9)") (class "Default")
      (node (ref "B1") (pin "V9") (pinfunction "IO_237_V9") (pintype "passive"))
    )
    (net (code "379") (name "unconnected-(B1-IO_238-PadV10)") (class "Default")
      (node (ref "B1") (pin "V10") (pinfunction "IO_238_V10") (pintype "passive"))
    )
    (net (code "380") (name "unconnected-(B1-IO_239-PadV11)") (class "Default")
      (node (ref "B1") (pin "V11") (pinfunction "IO_239_V11") (pintype "passive"))
    )
    (net (code "381") (name "unconnected-(B1-IO_240-PadV12)") (class "Default")
      (node (ref "B1") (pin "V12") (pinfunction "IO_240_V12") (pintype "passive"))
    )
    (net (code "382") (name "unconnected-(B1-IO_241-PadV13)") (class "Default")
      (node (ref "B1") (pin "V13") (pinfunction "IO_241_V13") (pintype "passive"))
    )
    (net (code "383") (name "unconnected-(B1-IO_242-PadV14)") (class "Default")
      (node (ref "B1") (pin "V14") (pinfunction "IO_242_V14") (pintype "passive"))
    )
    (net (code "384") (name "unconnected-(B1-IO_243-PadV15)") (class "Default")
      (node (ref "B1") (pin "V15") (pinfunction "IO_243_V15") (pintype "passive"))
    )
    (net (code "385") (name "unconnected-(B1-IO_244-PadV16)") (class "Default")
      (node (ref "B1") (pin "V16") (pinfunction "IO_244_V16") (pintype "passive"))
    )
    (net (code "386") (name "unconnected-(B1-IO_249-PadW6)") (class "Default")
      (node (ref "B1") (pin "W6") (pinfunction "IO_249_W6") (pintype "passive"))
    )
    (net (code "387") (name "unconnected-(B1-IO_250-PadW7)") (class "Default")
      (node (ref "B1") (pin "W7") (pinfunction "IO_250_W7") (pintype "passive"))
    )
    (net (code "388") (name "unconnected-(B1-IO_251-PadW8)") (class "Default")
      (node (ref "B1") (pin "W8") (pinfunction "IO_251_W8") (pintype "passive"))
    )
    (net (code "389") (name "unconnected-(B1-IO_252-PadW10)") (class "Default")
      (node (ref "B1") (pin "W10") (pinfunction "IO_252_W10") (pintype "passive"))
    )
    (net (code "390") (name "unconnected-(B1-IO_253-PadW13)") (class "Default")
      (node (ref "B1") (pin "W13") (pinfunction "IO_253_W13") (pintype "passive"))
    )
    (net (code "391") (name "unconnected-(B1-IO_254-PadW14)") (class "Default")
      (node (ref "B1") (pin "W14") (pinfunction "IO_254_W14") (pintype "passive"))
    )
    (net (code "392") (name "unconnected-(B1-IO_255-PadW15)") (class "Default")
      (node (ref "B1") (pin "W15") (pinfunction "IO_255_W15") (pintype "passive"))
    )
    (net (code "393") (name "unconnected-(B1-IO_256-PadW17)") (class "Default")
      (node (ref "B1") (pin "W17") (pinfunction "IO_256_W17") (pintype "passive"))
    )
    (net (code "394") (name "unconnected-(B1-IO_257-PadW19)") (class "Default")
      (node (ref "B1") (pin "W19") (pinfunction "IO_257_W19") (pintype "passive"))
    )
    (net (code "395") (name "unconnected-(B1-IO_258-PadW20)") (class "Default")
      (node (ref "B1") (pin "W20") (pinfunction "IO_258_W20") (pintype "passive"))
    )
    (net (code "396") (name "unconnected-(B1-IO_263-PadY3)") (class "Default")
      (node (ref "B1") (pin "Y3") (pinfunction "IO_263_Y3") (pintype "passive"))
    )
    (net (code "397") (name "unconnected-(B1-IO_264-PadY4)") (class "Default")
      (node (ref "B1") (pin "Y4") (pinfunction "IO_264_Y4") (pintype "passive"))
    )
    (net (code "398") (name "unconnected-(B1-IO_265-PadY6)") (class "Default")
      (node (ref "B1") (pin "Y6") (pinfunction "IO_265_Y6") (pintype "passive"))
    )
    (net (code "399") (name "unconnected-(B1-IO_266-PadY7)") (class "Default")
      (node (ref "B1") (pin "Y7") (pinfunction "IO_266_Y7") (pintype "passive"))
    )
    (net (code "400") (name "unconnected-(B1-IO_267-PadY8)") (class "Default")
      (node (ref "B1") (pin "Y8") (pinfunction "IO_267_Y8") (pintype "passive"))
    )
    (net (code "401") (name "unconnected-(B1-IO_268-PadY10)") (class "Default")
      (node (ref "B1") (pin "Y10") (pinfunction "IO_268_Y10") (pintype "passive"))
    )
    (net (code "402") (name "unconnected-(B1-IO_269-PadY13)") (class "Default")
      (node (ref "B1") (pin "Y13") (pinfunction "IO_269_Y13") (pintype "passive"))
    )
    (net (code "403") (name "unconnected-(B1-IO_270-PadY14)") (class "Default")
      (node (ref "B1") (pin "Y14") (pinfunction "IO_270_Y14") (pintype "passive"))
    )
    (net (code "404") (name "unconnected-(B1-IO_271-PadY15)") (class "Default")
      (node (ref "B1") (pin "Y15") (pinfunction "IO_271_Y15") (pintype "passive"))
    )
    (net (code "405") (name "unconnected-(B1-IO_272-PadY17)") (class "Default")
      (node (ref "B1") (pin "Y17") (pinfunction "IO_272_Y17") (pintype "passive"))
    )
    (net (code "406") (name "unconnected-(B1-MSEL0-PadM17)") (class "Default")
      (node (ref "B1") (pin "M17") (pinfunction "MSEL0_M17") (pintype "passive"))
    )
    (net (code "407") (name "unconnected-(B1-MSEL1-PadL18)") (class "Default")
      (node (ref "B1") (pin "L18") (pinfunction "MSEL1_L18") (pintype "passive"))
    )
    (net (code "408") (name "unconnected-(B1-MSEL2-PadL17)") (class "Default")
      (node (ref "B1") (pin "L17") (pinfunction "MSEL2_L17") (pintype "passive"))
    )
    (net (code "409") (name "unconnected-(B1-MSEL3-PadK20)") (class "Default")
      (node (ref "B1") (pin "K20") (pinfunction "MSEL3_K20") (pintype "passive"))
    )
    (net (code "410") (name "unconnected-(B1-NCE-PadL3)") (class "Default")
      (node (ref "B1") (pin "L3") (pinfunction "NCE_L3") (pintype "passive"))
    )
    (net (code "411") (name "unconnected-(B1-NCONFIG-PadK5)") (class "Default")
      (node (ref "B1") (pin "K5") (pinfunction "NCONFIG_K5") (pintype "passive"))
    )
    (net (code "412") (name "unconnected-(B1-NSTATUS-PadK6)") (class "Default")
      (node (ref "B1") (pin "K6") (pinfunction "NSTATUS_K6") (pintype "passive"))
    )
    (net (code "413") (name "unconnected-(B1-TDI-PadL5)") (class "Default")
      (node (ref "B1") (pin "L5") (pinfunction "TDI_L5") (pintype "passive"))
    )
    (net (code "414") (name "unconnected-(B1-TDO-PadL4)") (class "Default")
      (node (ref "B1") (pin "L4") (pinfunction "TDO_L4") (pintype "passive"))
    )
    (net (code "415") (name "unconnected-(B1-VCCA1-PadT6)") (class "Default")
      (node (ref "B1") (pin "T6") (pinfunction "VCCA1_T6") (pintype "passive"))
    )
    (net (code "416") (name "unconnected-(B1-VCCA2-PadF18)") (class "Default")
      (node (ref "B1") (pin "F18") (pinfunction "VCCA2_F18") (pintype "passive"))
    )
    (net (code "417") (name "unconnected-(B1-VCCA3-PadG6)") (class "Default")
      (node (ref "B1") (pin "G6") (pinfunction "VCCA3_G6") (pintype "passive"))
    )
    (net (code "418") (name "unconnected-(B1-VCCA4-PadU18)") (class "Default")
      (node (ref "B1") (pin "U18") (pinfunction "VCCA4_U18") (pintype "passive"))
    )
    (net (code "419") (name "unconnected-(B1-VCCD_PLL1-PadU6)") (class "Default")
      (node (ref "B1") (pin "U6") (pinfunction "VCCD_PLL1_U6") (pintype "passive"))
    )
    (net (code "420") (name "unconnected-(B1-VCCD_PLL2-PadE17)") (class "Default")
      (node (ref "B1") (pin "E17") (pinfunction "VCCD_PLL2_E17") (pintype "passive"))
    )
    (net (code "421") (name "unconnected-(B1-VCCD_PLL3-PadF6)") (class "Default")
      (node (ref "B1") (pin "F6") (pinfunction "VCCD_PLL3_F6") (pintype "passive"))
    )
    (net (code "422") (name "unconnected-(B1-VCCD_PLL4-PadV17)") (class "Default")
      (node (ref "B1") (pin "V17") (pinfunction "VCCD_PLL4_V17") (pintype "passive"))
    )
    (net (code "423") (name "unconnected-(B1-VCCINT_1-PadG12)") (class "Default")
      (node (ref "B1") (pin "G12") (pinfunction "VCCINT_1_G12") (pintype "passive"))
    )
    (net (code "424") (name "unconnected-(B1-VCCINT_2-PadH9)") (class "Default")
      (node (ref "B1") (pin "H9") (pinfunction "VCCINT_2_H9") (pintype "passive"))
    )
    (net (code "425") (name "unconnected-(B1-VCCINT_3-PadH11)") (class "Default")
      (node (ref "B1") (pin "H11") (pinfunction "VCCINT_3_H11") (pintype "passive"))
    )
    (net (code "426") (name "unconnected-(B1-VCCINT_4-PadH15)") (class "Default")
      (node (ref "B1") (pin "H15") (pinfunction "VCCINT_4_H15") (pintype "passive"))
    )
    (net (code "427") (name "unconnected-(B1-VCCINT_5-PadJ8)") (class "Default")
      (node (ref "B1") (pin "J8") (pinfunction "VCCINT_5_J8") (pintype "passive"))
    )
    (net (code "428") (name "unconnected-(B1-VCCINT_6-PadJ10)") (class "Default")
      (node (ref "B1") (pin "J10") (pinfunction "VCCINT_6_J10") (pintype "passive"))
    )
    (net (code "429") (name "unconnected-(B1-VCCINT_7-PadJ11)") (class "Default")
      (node (ref "B1") (pin "J11") (pinfunction "VCCINT_7_J11") (pintype "passive"))
    )
    (net (code "430") (name "unconnected-(B1-VCCINT_8-PadJ12)") (class "Default")
      (node (ref "B1") (pin "J12") (pinfunction "VCCINT_8_J12") (pintype "passive"))
    )
    (net (code "431") (name "unconnected-(B1-VCCINT_9-PadJ13)") (class "Default")
      (node (ref "B1") (pin "J13") (pinfunction "VCCINT_9_J13") (pintype "passive"))
    )
    (net (code "432") (name "unconnected-(B1-VCCINT_10-PadJ14)") (class "Default")
      (node (ref "B1") (pin "J14") (pinfunction "VCCINT_10_J14") (pintype "passive"))
    )
    (net (code "433") (name "unconnected-(B1-VCCINT_11-PadJ16)") (class "Default")
      (node (ref "B1") (pin "J16") (pinfunction "VCCINT_11_J16") (pintype "passive"))
    )
    (net (code "434") (name "unconnected-(B1-VCCINT_12-PadK8)") (class "Default")
      (node (ref "B1") (pin "K8") (pinfunction "VCCINT_12_K8") (pintype "passive"))
    )
    (net (code "435") (name "unconnected-(B1-VCCINT_13-PadK9)") (class "Default")
      (node (ref "B1") (pin "K9") (pinfunction "VCCINT_13_K9") (pintype "passive"))
    )
    (net (code "436") (name "unconnected-(B1-VCCINT_14-PadK14)") (class "Default")
      (node (ref "B1") (pin "K14") (pinfunction "VCCINT_14_K14") (pintype "passive"))
    )
    (net (code "437") (name "unconnected-(B1-VCCINT_15-PadK15)") (class "Default")
      (node (ref "B1") (pin "K15") (pinfunction "VCCINT_15_K15") (pintype "passive"))
    )
    (net (code "438") (name "unconnected-(B1-VCCINT_16-PadL7)") (class "Default")
      (node (ref "B1") (pin "L7") (pinfunction "VCCINT_16_L7") (pintype "passive"))
    )
    (net (code "439") (name "unconnected-(B1-VCCINT_17-PadL9)") (class "Default")
      (node (ref "B1") (pin "L9") (pinfunction "VCCINT_17_L9") (pintype "passive"))
    )
    (net (code "440") (name "unconnected-(B1-VCCINT_18-PadL14)") (class "Default")
      (node (ref "B1") (pin "L14") (pinfunction "VCCINT_18_L14") (pintype "passive"))
    )
    (net (code "441") (name "unconnected-(B1-VCCINT_19-PadL16)") (class "Default")
      (node (ref "B1") (pin "L16") (pinfunction "VCCINT_19_L16") (pintype "passive"))
    )
    (net (code "442") (name "unconnected-(B1-VCCINT_20-PadM8)") (class "Default")
      (node (ref "B1") (pin "M8") (pinfunction "VCCINT_20_M8") (pintype "passive"))
    )
    (net (code "443") (name "unconnected-(B1-VCCINT_21-PadM9)") (class "Default")
      (node (ref "B1") (pin "M9") (pinfunction "VCCINT_21_M9") (pintype "passive"))
    )
    (net (code "444") (name "unconnected-(B1-VCCINT_22-PadM14)") (class "Default")
      (node (ref "B1") (pin "M14") (pinfunction "VCCINT_22_M14") (pintype "passive"))
    )
    (net (code "445") (name "unconnected-(B1-VCCINT_23-PadM15)") (class "Default")
      (node (ref "B1") (pin "M15") (pinfunction "VCCINT_23_M15") (pintype "passive"))
    )
    (net (code "446") (name "unconnected-(B1-VCCINT_24-PadN9)") (class "Default")
      (node (ref "B1") (pin "N9") (pinfunction "VCCINT_24_N9") (pintype "passive"))
    )
    (net (code "447") (name "unconnected-(B1-VCCINT_25-PadN14)") (class "Default")
      (node (ref "B1") (pin "N14") (pinfunction "VCCINT_25_N14") (pintype "passive"))
    )
    (net (code "448") (name "unconnected-(B1-VCCINT_26-PadP9)") (class "Default")
      (node (ref "B1") (pin "P9") (pinfunction "VCCINT_26_P9") (pintype "passive"))
    )
    (net (code "449") (name "unconnected-(B1-VCCINT_27-PadP10)") (class "Default")
      (node (ref "B1") (pin "P10") (pinfunction "VCCINT_27_P10") (pintype "passive"))
    )
    (net (code "450") (name "unconnected-(B1-VCCINT_28-PadP11)") (class "Default")
      (node (ref "B1") (pin "P11") (pinfunction "VCCINT_28_P11") (pintype "passive"))
    )
    (net (code "451") (name "unconnected-(B1-VCCINT_29-PadP12)") (class "Default")
      (node (ref "B1") (pin "P12") (pinfunction "VCCINT_29_P12") (pintype "passive"))
    )
    (net (code "452") (name "unconnected-(B1-VCCINT_30-PadP13)") (class "Default")
      (node (ref "B1") (pin "P13") (pinfunction "VCCINT_30_P13") (pintype "passive"))
    )
    (net (code "453") (name "unconnected-(B1-VCCINT_31-PadP14)") (class "Default")
      (node (ref "B1") (pin "P14") (pinfunction "VCCINT_31_P14") (pintype "passive"))
    )
    (net (code "454") (name "unconnected-(B1-VCCINT_32-PadP15)") (class "Default")
      (node (ref "B1") (pin "P15") (pinfunction "VCCINT_32_P15") (pintype "passive"))
    )
    (net (code "455") (name "unconnected-(B1-VCCINT_33-PadR8)") (class "Default")
      (node (ref "B1") (pin "R8") (pinfunction "VCCINT_33_R8") (pintype "passive"))
    )
    (net (code "456") (name "unconnected-(B1-VCCINT_34-PadR10)") (class "Default")
      (node (ref "B1") (pin "R10") (pinfunction "VCCINT_34_R10") (pintype "passive"))
    )
    (net (code "457") (name "unconnected-(B1-VCCINT_35-PadR12)") (class "Default")
      (node (ref "B1") (pin "R12") (pinfunction "VCCINT_35_R12") (pintype "passive"))
    )
    (net (code "458") (name "unconnected-(B1-VCCINT_36-PadT7)") (class "Default")
      (node (ref "B1") (pin "T7") (pinfunction "VCCINT_36_T7") (pintype "passive"))
    )
    (net (code "459") (name "unconnected-(B1-VCCINT_37-PadT9)") (class "Default")
      (node (ref "B1") (pin "T9") (pinfunction "VCCINT_37_T9") (pintype "passive"))
    )
    (net (code "460") (name "unconnected-(B1-VCCINT_38-PadT13)") (class "Default")
      (node (ref "B1") (pin "T13") (pinfunction "VCCINT_38_T13") (pintype "passive"))
    )
    (net (code "461") (name "unconnected-(B1-VCCIO1_1-PadD4)") (class "Default")
      (node (ref "B1") (pin "D4") (pinfunction "VCCIO1_1_D4") (pintype "passive"))
    )
    (net (code "462") (name "unconnected-(B1-VCCIO1_2-PadF4)") (class "Default")
      (node (ref "B1") (pin "F4") (pinfunction "VCCIO1_2_F4") (pintype "passive"))
    )
    (net (code "463") (name "unconnected-(B1-VCCIO1_3-PadK4)") (class "Default")
      (node (ref "B1") (pin "K4") (pinfunction "VCCIO1_3_K4") (pintype "passive"))
    )
    (net (code "464") (name "unconnected-(B1-VCCIO2_1-PadN4)") (class "Default")
      (node (ref "B1") (pin "N4") (pinfunction "VCCIO2_1_N4") (pintype "passive"))
    )
    (net (code "465") (name "unconnected-(B1-VCCIO2_2-PadU4)") (class "Default")
      (node (ref "B1") (pin "U4") (pinfunction "VCCIO2_2_U4") (pintype "passive"))
    )
    (net (code "466") (name "unconnected-(B1-VCCIO2_3-PadW4)") (class "Default")
      (node (ref "B1") (pin "W4") (pinfunction "VCCIO2_3_W4") (pintype "passive"))
    )
    (net (code "467") (name "unconnected-(B1-VCCIO3_1-PadW5)") (class "Default")
      (node (ref "B1") (pin "W5") (pinfunction "VCCIO3_1_W5") (pintype "passive"))
    )
    (net (code "468") (name "unconnected-(B1-VCCIO3_2-PadW9)") (class "Default")
      (node (ref "B1") (pin "W9") (pinfunction "VCCIO3_2_W9") (pintype "passive"))
    )
    (net (code "469") (name "unconnected-(B1-VCCIO3_3-PadW11)") (class "Default")
      (node (ref "B1") (pin "W11") (pinfunction "VCCIO3_3_W11") (pintype "passive"))
    )
    (net (code "470") (name "unconnected-(B1-VCCIO4_1-PadW12)") (class "Default")
      (node (ref "B1") (pin "W12") (pinfunction "VCCIO4_1_W12") (pintype "passive"))
    )
    (net (code "471") (name "unconnected-(B1-VCCIO4_2-PadW16)") (class "Default")
      (node (ref "B1") (pin "W16") (pinfunction "VCCIO4_2_W16") (pintype "passive"))
    )
    (net (code "472") (name "unconnected-(B1-VCCIO4_3-PadW18)") (class "Default")
      (node (ref "B1") (pin "W18") (pinfunction "VCCIO4_3_W18") (pintype "passive"))
    )
    (net (code "473") (name "unconnected-(B1-VCCIO5_1-PadP18)") (class "Default")
      (node (ref "B1") (pin "P18") (pinfunction "VCCIO5_1_P18") (pintype "passive"))
    )
    (net (code "474") (name "unconnected-(B1-VCCIO5_2-PadV19)") (class "Default")
      (node (ref "B1") (pin "V19") (pinfunction "VCCIO5_2_V19") (pintype "passive"))
    )
    (net (code "475") (name "unconnected-(B1-VCCIO5_3-PadY19)") (class "Default")
      (node (ref "B1") (pin "Y19") (pinfunction "VCCIO5_3_Y19") (pintype "passive"))
    )
    (net (code "476") (name "unconnected-(B1-VCCIO6_1-PadE19)") (class "Default")
      (node (ref "B1") (pin "E19") (pinfunction "VCCIO6_1_E19") (pintype "passive"))
    )
    (net (code "477") (name "unconnected-(B1-VCCIO6_2-PadG19)") (class "Default")
      (node (ref "B1") (pin "G19") (pinfunction "VCCIO6_2_G19") (pintype "passive"))
    )
    (net (code "478") (name "unconnected-(B1-VCCIO6_3-PadL19)") (class "Default")
      (node (ref "B1") (pin "L19") (pinfunction "VCCIO6_3_L19") (pintype "passive"))
    )
    (net (code "479") (name "unconnected-(B1-VCCIO7_2-PadD12)") (class "Default")
      (node (ref "B1") (pin "D12") (pinfunction "VCCIO7_2_D12") (pintype "passive"))
    )
    (net (code "480") (name "unconnected-(B1-VCCIO7_3-PadD14)") (class "Default")
      (node (ref "B1") (pin "D14") (pinfunction "VCCIO7_3_D14") (pintype "passive"))
    )
    (net (code "481") (name "unconnected-(B1-VCCIO7_4-PadD16)") (class "Default")
      (node (ref "B1") (pin "D16") (pinfunction "VCCIO7_4_D16") (pintype "passive"))
    )
    (net (code "482") (name "unconnected-(B1-VCCIO8_2-PadD5)") (class "Default")
      (node (ref "B1") (pin "D5") (pinfunction "VCCIO8_2_D5") (pintype "passive"))
    )
    (net (code "483") (name "unconnected-(B1-VCCIO8_3-PadD9)") (class "Default")
      (node (ref "B1") (pin "D9") (pinfunction "VCCIO8_3_D9") (pintype "passive"))
    )
    (net (code "484") (name "unconnected-(B1-VCCIO8_4-PadD11)") (class "Default")
      (node (ref "B1") (pin "D11") (pinfunction "VCCIO8_4_D11") (pintype "passive"))
    )
  )
)
